# proxmark3.net
KiCad netlist of a schematic drawn in EAGLE
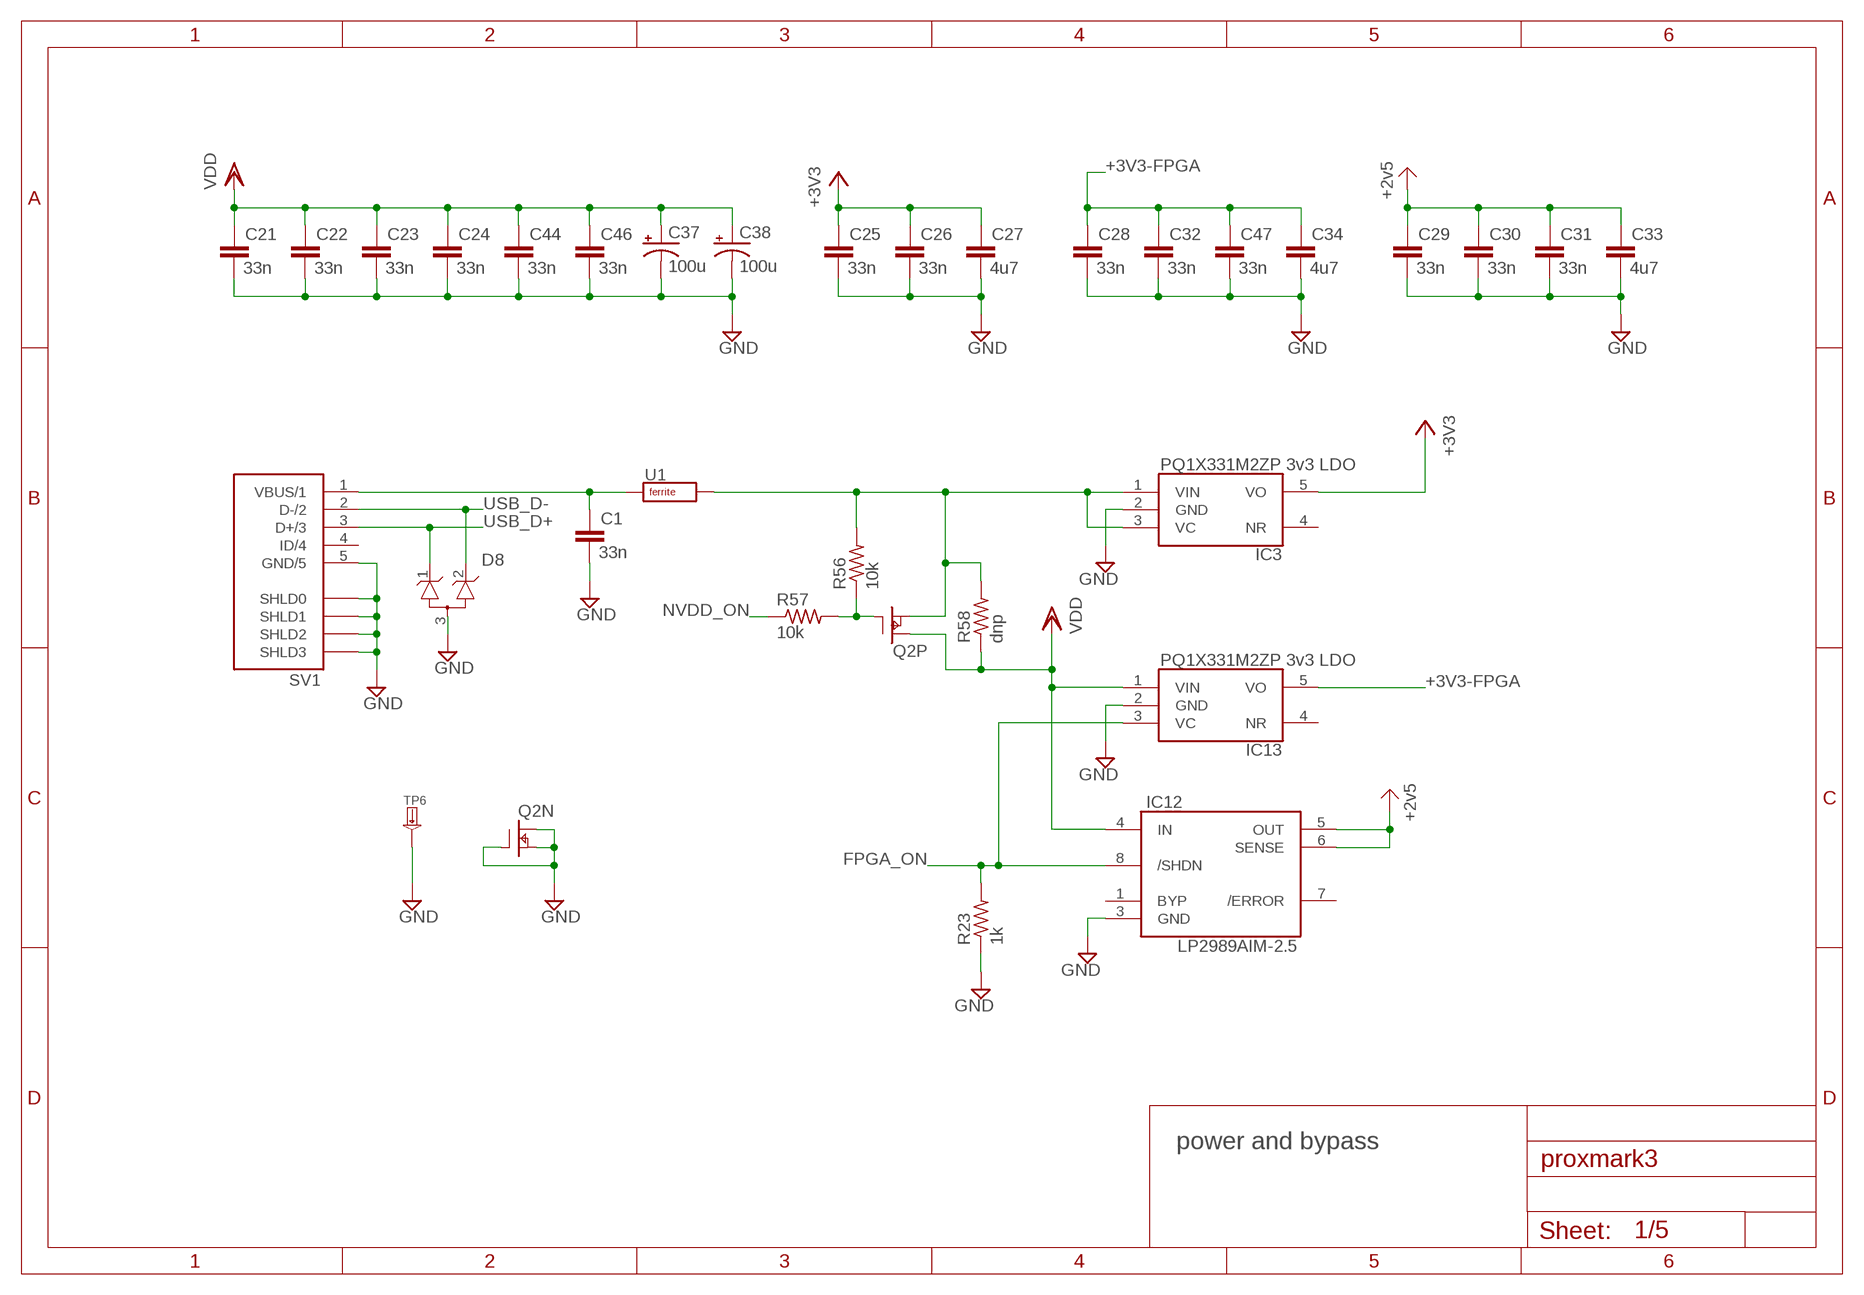
[diagram p0: schematic, sheet 1]
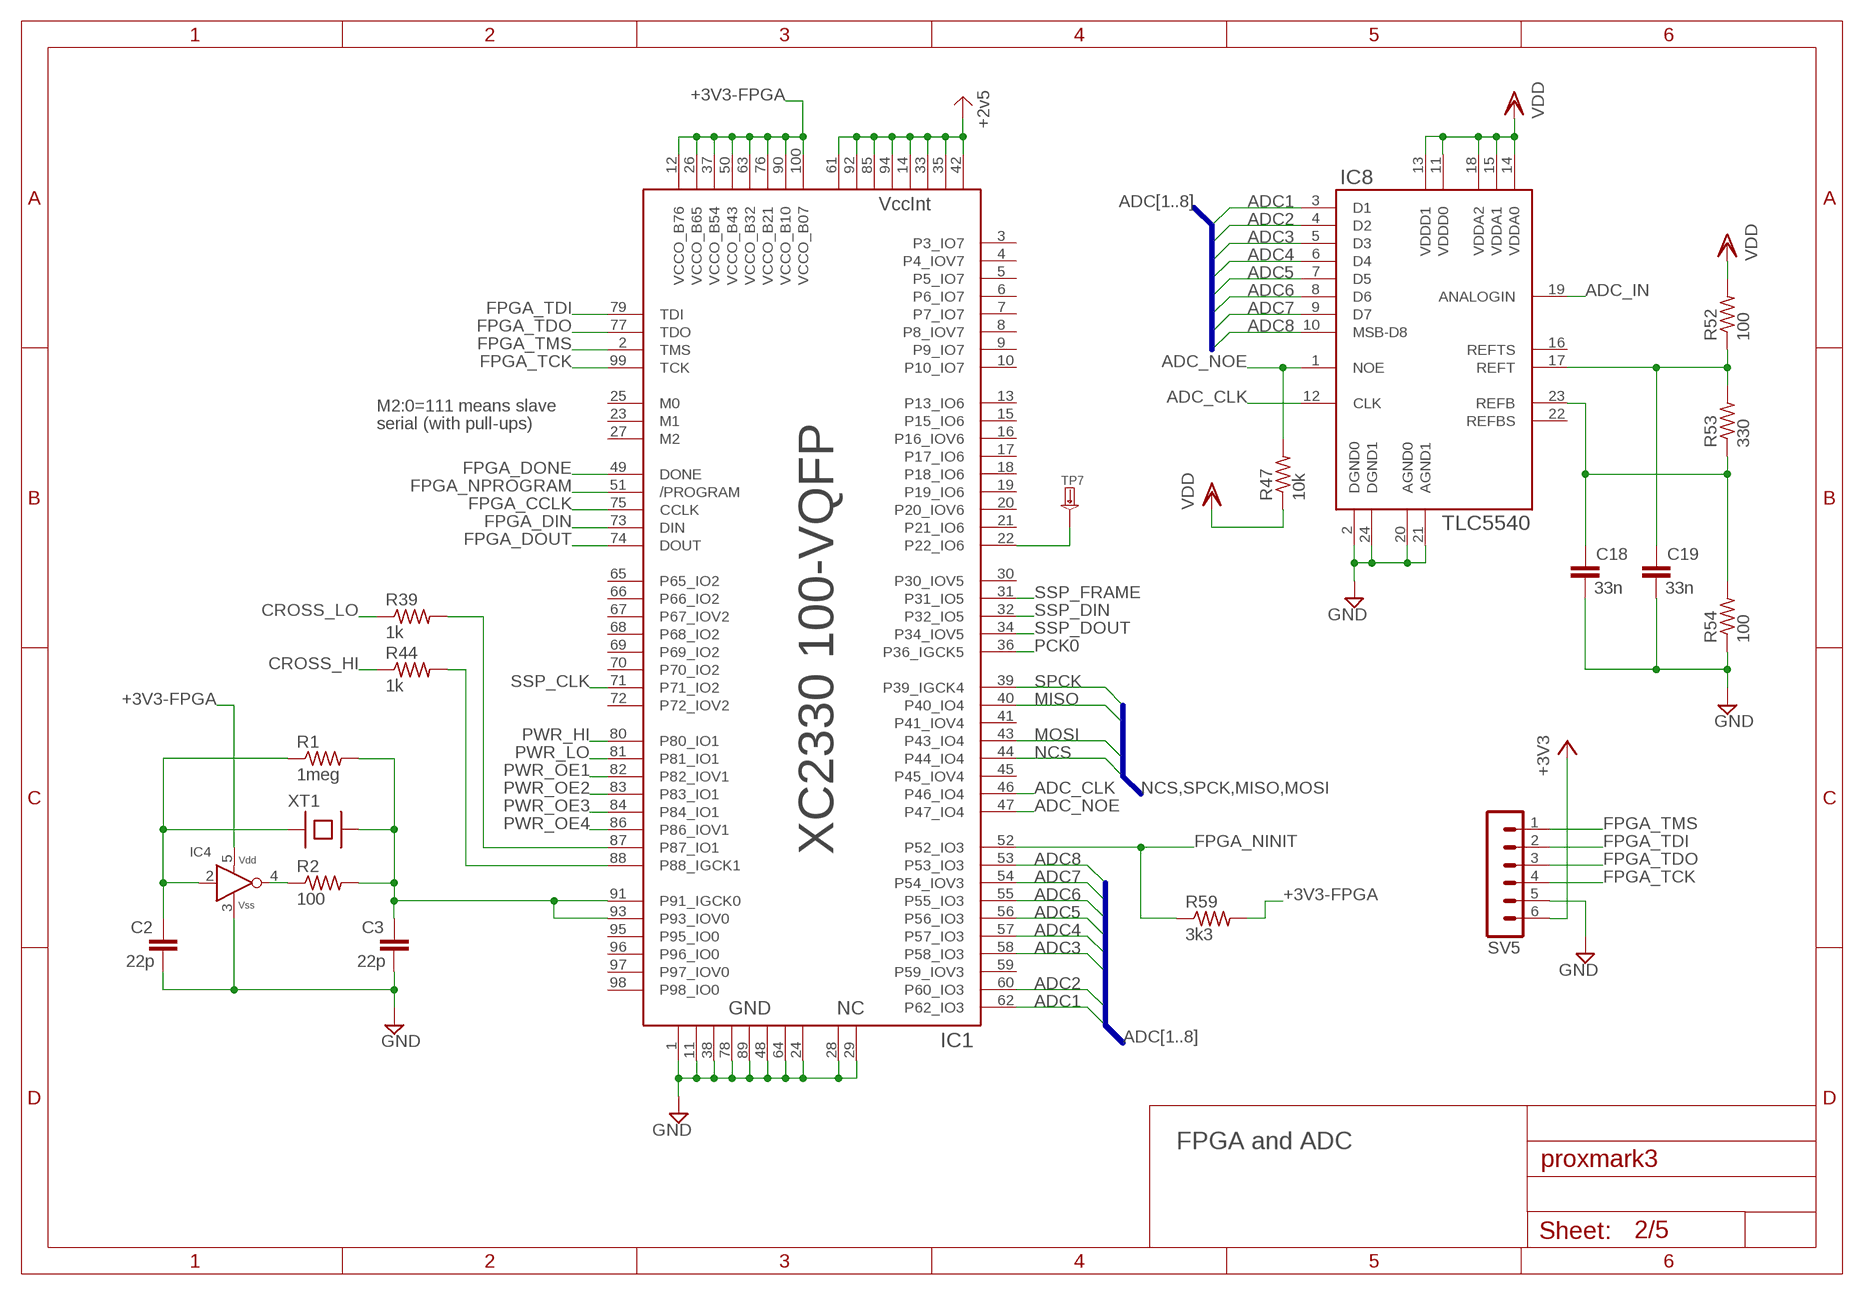
[diagram p1: schematic, sheet 2]
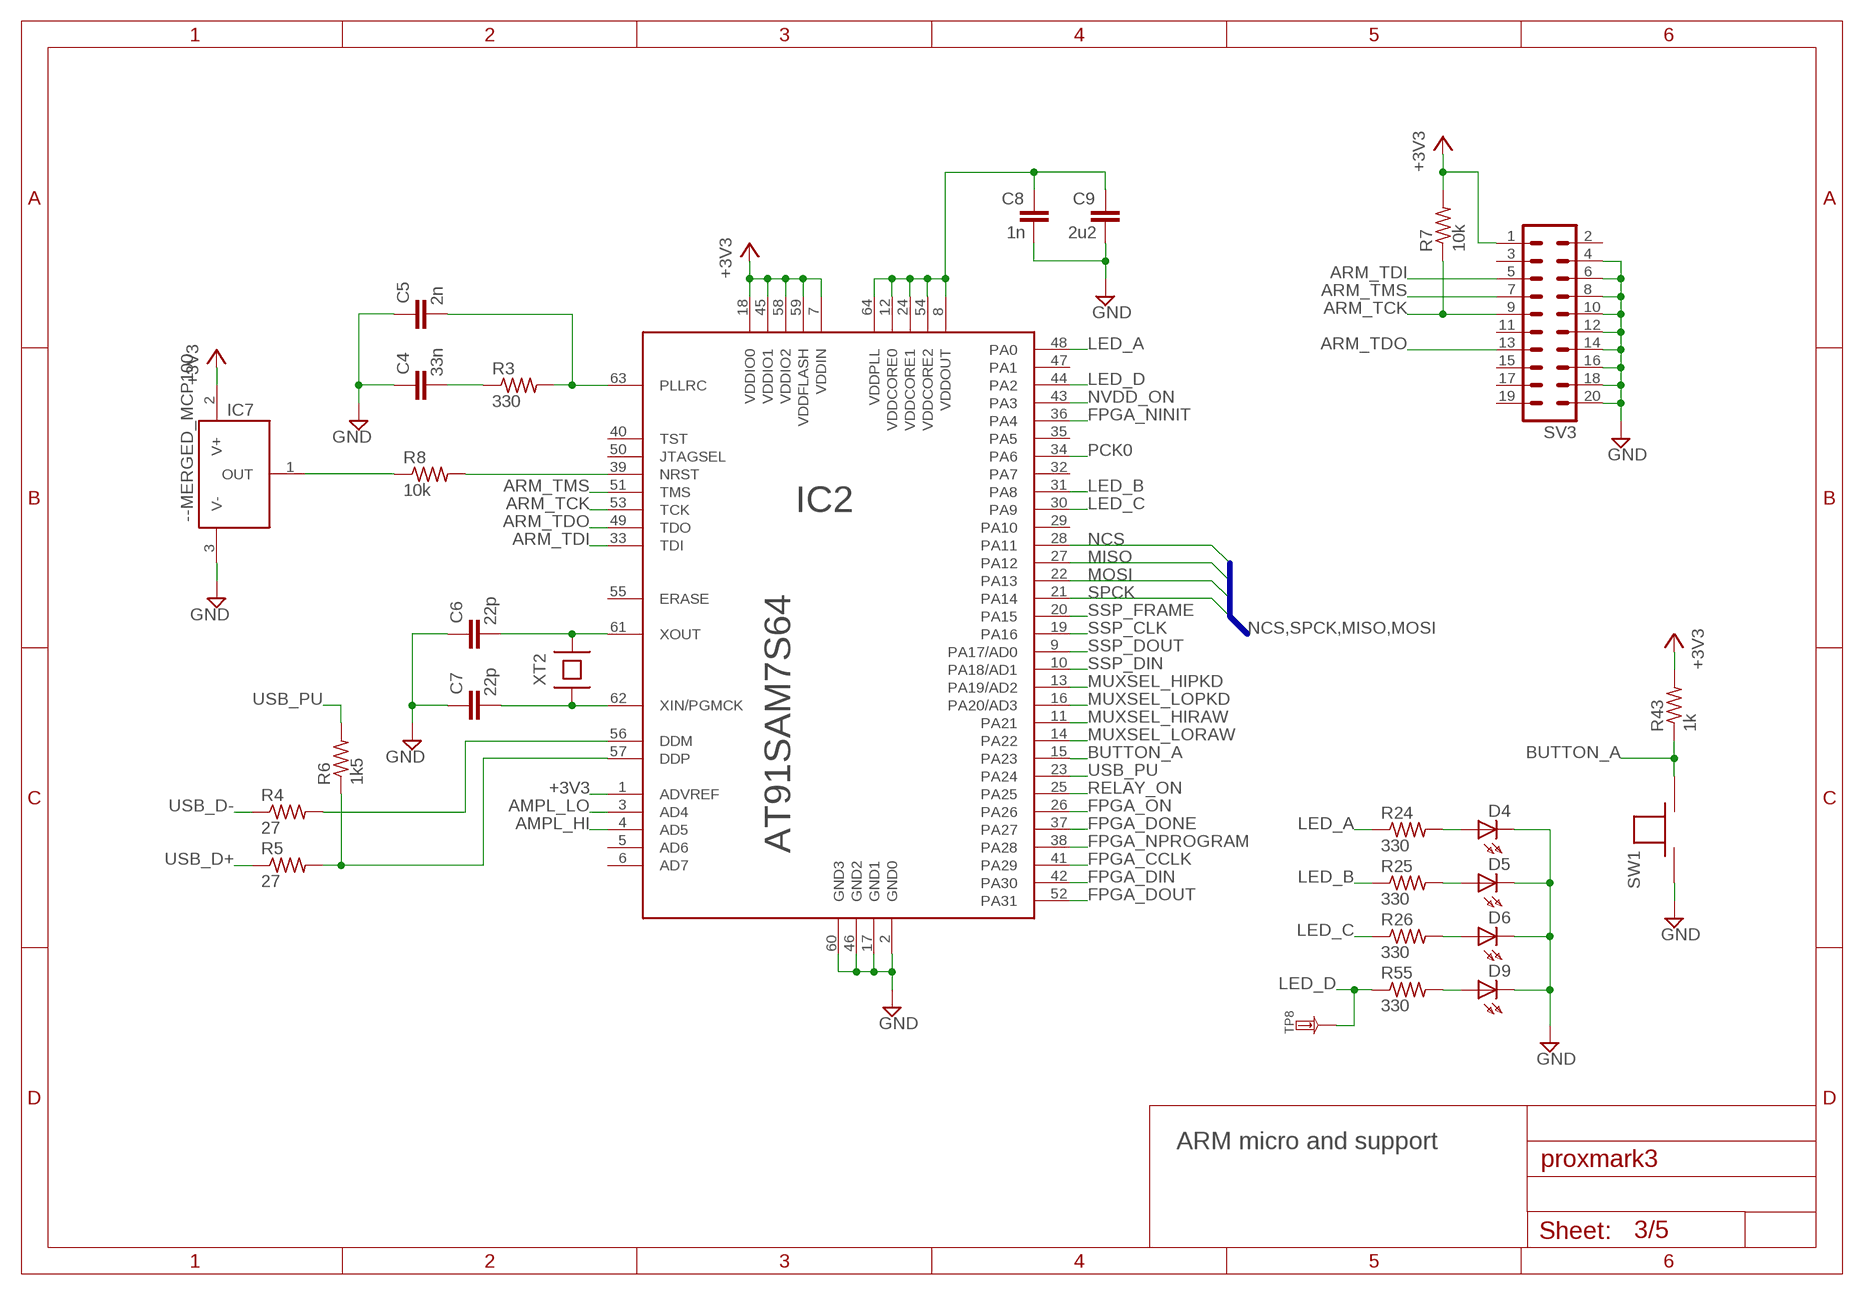
[diagram p2: schematic, sheet 3]
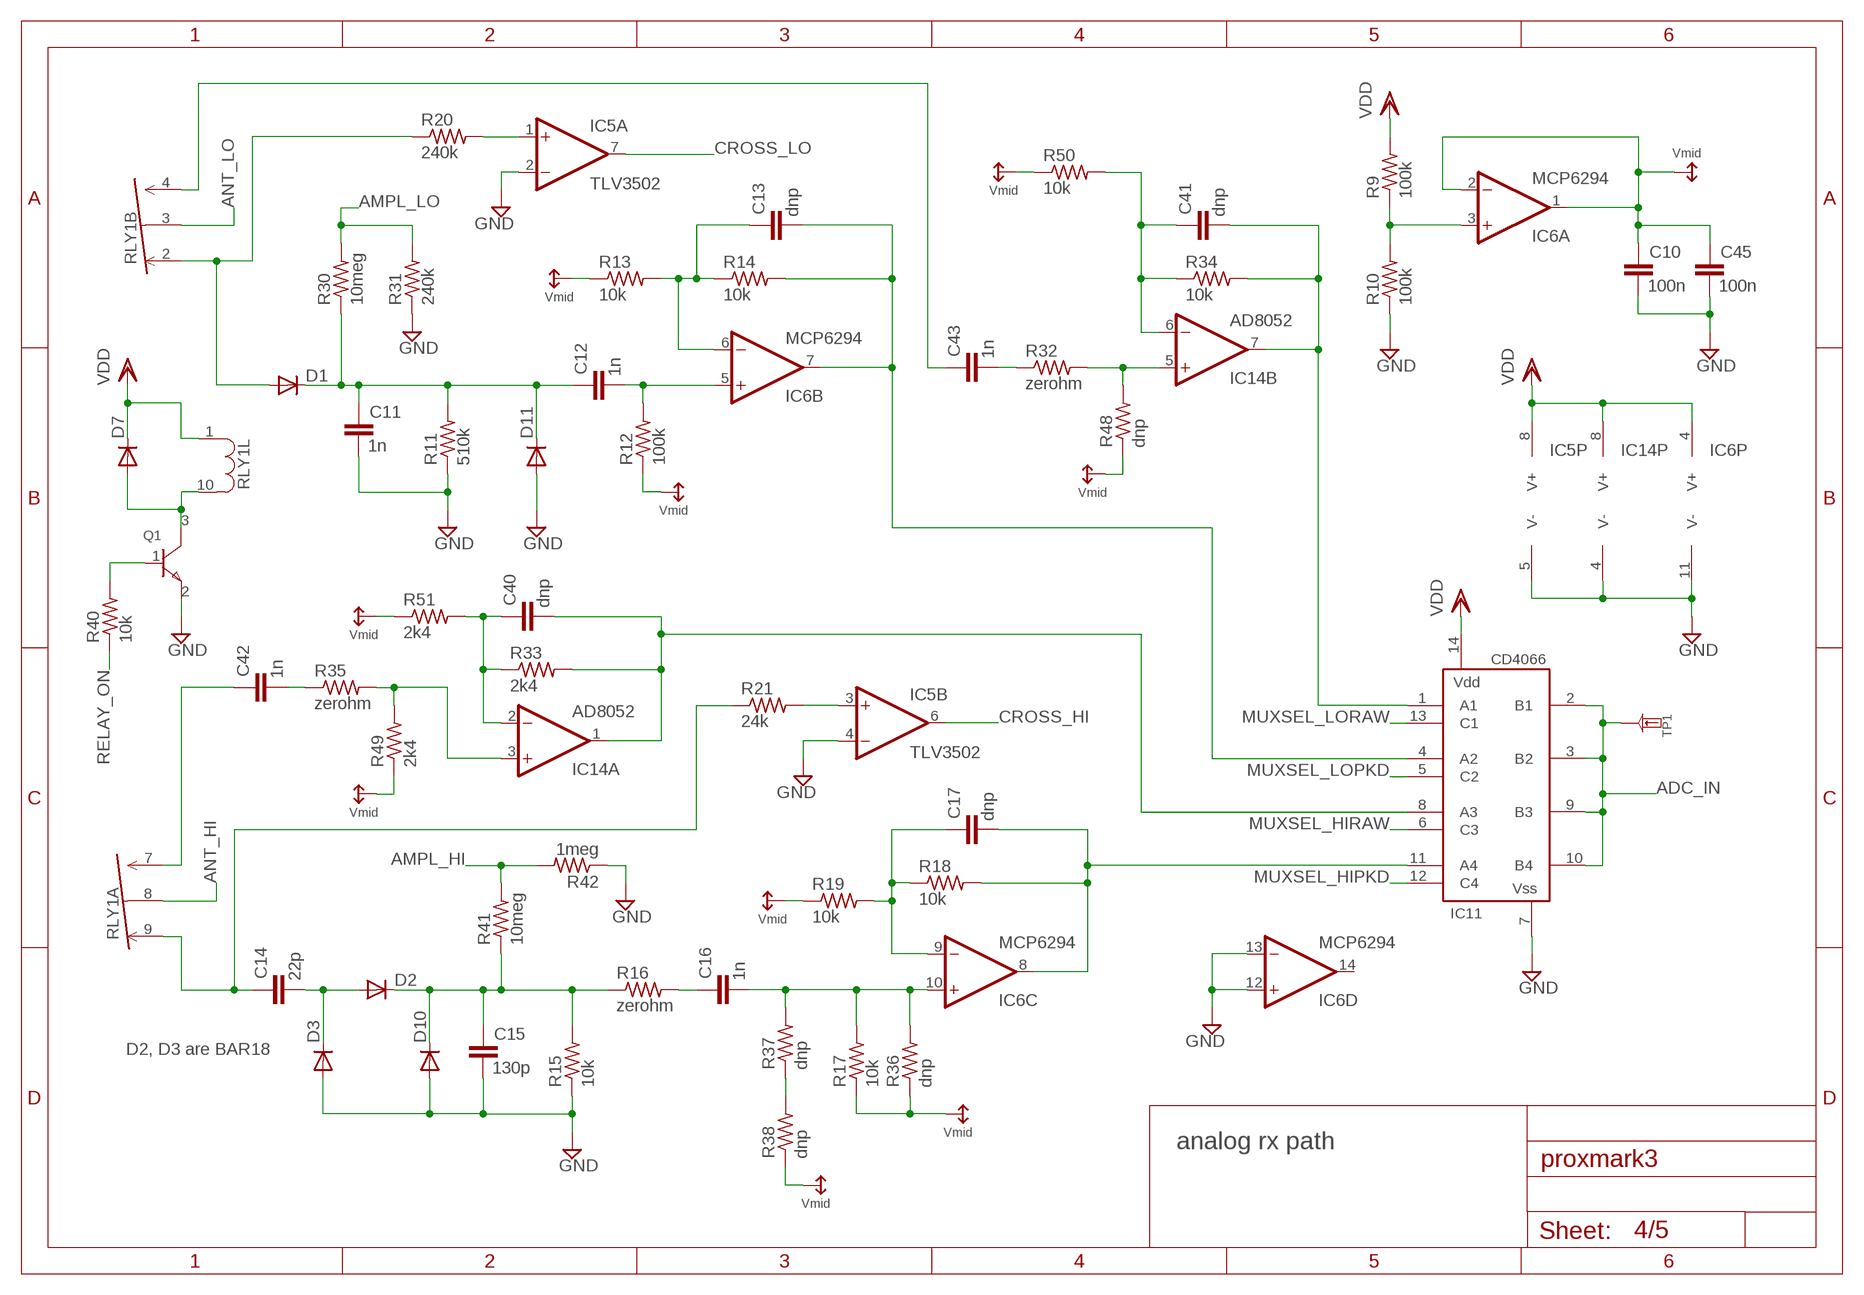
[diagram p3: schematic, sheet 4]
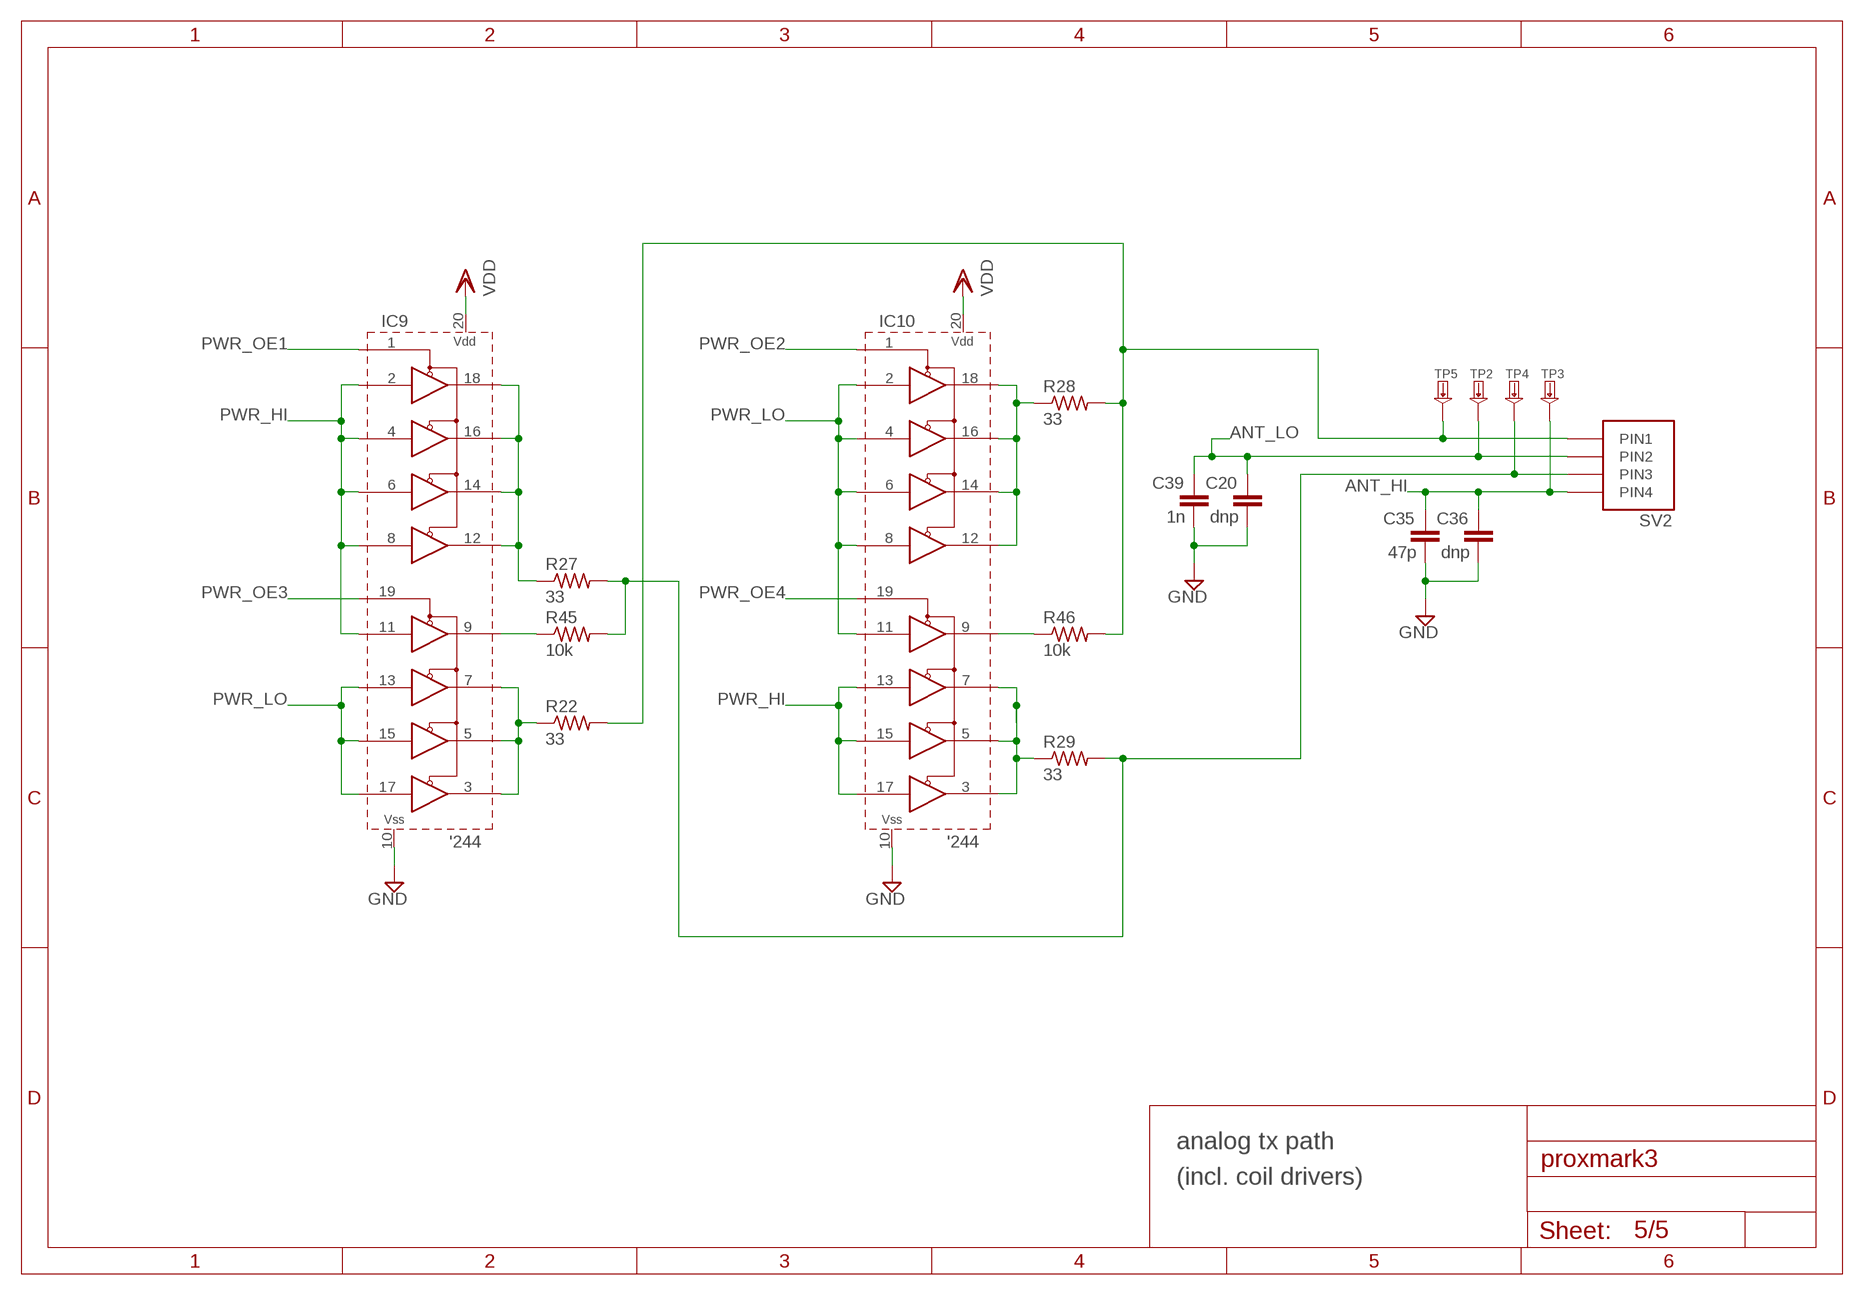
[diagram p4: schematic, sheet 5]

(export (version "E")
  (design (tool "Eeschema 10.0.6"))
  (components
    (comp (ref "C1")
      (value "33n")
      (footprint "eagle-import:RLC_0603")
      (libsource (lib "eagle-import") (part "CAPACITOR0603"))
    )
    (comp (ref "C21")
      (value "33n")
      (footprint "eagle-import:RLC_0603")
      (libsource (lib "eagle-import") (part "CAPACITOR0603"))
    )
    (comp (ref "C22")
      (value "33n")
      (footprint "eagle-import:RLC_0603")
      (libsource (lib "eagle-import") (part "CAPACITOR0603"))
    )
    (comp (ref "C23")
      (value "33n")
      (footprint "eagle-import:RLC_0603")
      (libsource (lib "eagle-import") (part "CAPACITOR0603"))
    )
    (comp (ref "C24")
      (value "33n")
      (footprint "eagle-import:RLC_0603")
      (libsource (lib "eagle-import") (part "CAPACITOR0603"))
    )
    (comp (ref "C25")
      (value "33n")
      (footprint "eagle-import:RLC_0603")
      (libsource (lib "eagle-import") (part "CAPACITOR0603"))
    )
    (comp (ref "C26")
      (value "33n")
      (footprint "eagle-import:RLC_0603")
      (libsource (lib "eagle-import") (part "CAPACITOR0603"))
    )
    (comp (ref "C27")
      (value "4u7")
      (footprint "eagle-import:RLC_1210")
      (libsource (lib "eagle-import") (part "CAPACITOR1210"))
    )
    (comp (ref "C28")
      (value "33n")
      (footprint "eagle-import:RLC_0603")
      (libsource (lib "eagle-import") (part "CAPACITOR0603"))
    )
    (comp (ref "C29")
      (value "33n")
      (footprint "eagle-import:RLC_0603")
      (libsource (lib "eagle-import") (part "CAPACITOR0603"))
    )
    (comp (ref "C30")
      (value "33n")
      (footprint "eagle-import:RLC_0603")
      (libsource (lib "eagle-import") (part "CAPACITOR0603"))
    )
    (comp (ref "C31")
      (value "33n")
      (footprint "eagle-import:RLC_0603")
      (libsource (lib "eagle-import") (part "CAPACITOR0603"))
    )
    (comp (ref "C32")
      (value "33n")
      (footprint "eagle-import:RLC_0603")
      (libsource (lib "eagle-import") (part "CAPACITOR0603"))
    )
    (comp (ref "C33")
      (value "4u7")
      (footprint "eagle-import:RLC_1210")
      (libsource (lib "eagle-import") (part "CAPACITOR1210"))
    )
    (comp (ref "C34")
      (value "4u7")
      (footprint "eagle-import:RLC_1210")
      (libsource (lib "eagle-import") (part "CAPACITOR1210"))
    )
    (comp (ref "C37")
      (value "100u")
      (footprint "eagle-import:CAPCAITOR-ELECTROLYTIC-ALCHIP-MZA-F80")
      (libsource (lib "eagle-import") (part "CAPACITOR-POLARIZEDALCHIP-MZA-F80"))
    )
    (comp (ref "C38")
      (value "100u")
      (footprint "eagle-import:CAPCAITOR-ELECTROLYTIC-ALCHIP-MZA-F80")
      (libsource (lib "eagle-import") (part "CAPACITOR-POLARIZEDALCHIP-MZA-F80"))
    )
    (comp (ref "C44")
      (value "33n")
      (footprint "eagle-import:RLC_0603")
      (libsource (lib "eagle-import") (part "CAPACITOR0603"))
    )
    (comp (ref "C46")
      (value "33n")
      (footprint "eagle-import:RLC_0603")
      (libsource (lib "eagle-import") (part "CAPACITOR0603"))
    )
    (comp (ref "C47")
      (value "33n")
      (footprint "eagle-import:RLC_0603")
      (libsource (lib "eagle-import") (part "CAPACITOR0603"))
    )
    (comp (ref "D8")
      (value "--MERGED_DUAL-TVS-COMMON-ANODE")
      (footprint "eagle-import:--MERGED_SOT23-3LEAD")
      (libsource (lib "eagle-import") (part "--MERGED_DUAL-TVS-COMMON-ANODE"))
    )
    (comp (ref "IC3")
      (value "--MERGED_PQ1X331M2ZP-3V3-LDO-SOT-23-5")
      (footprint "eagle-import:--MERGED_SOT-23-5")
      (libsource (lib "eagle-import") (part "--MERGED_PQ1X331M2ZP-3V3-LDO-SOT-23-5"))
    )
    (comp (ref "IC12")
      (value "LP2989AIM-2.5")
      (footprint "eagle-import:SOIC-8")
      (libsource (lib "eagle-import") (part "LP2989-LDOSOIC"))
    )
    (comp (ref "IC13")
      (value "--MERGED_PQ1X331M2ZP-3V3-LDO-SOT-23-5")
      (footprint "eagle-import:--MERGED_SOT-23-5")
      (libsource (lib "eagle-import") (part "--MERGED_PQ1X331M2ZP-3V3-LDO-SOT-23-5"))
    )
    (comp (ref "Q2")
      (value "IRF7307")
      (footprint "eagle-import:SOIC-8")
      (libsource (lib "eagle-import") (part "IRF7307"))
    )
    (comp (ref "R23")
      (value "1k")
      (footprint "eagle-import:RLC_0603")
      (libsource (lib "eagle-import") (part "RESISTOR0603"))
    )
    (comp (ref "R56")
      (value "10k")
      (footprint "eagle-import:RLC_0603")
      (libsource (lib "eagle-import") (part "RESISTOR0603"))
    )
    (comp (ref "R57")
      (value "10k")
      (footprint "eagle-import:RLC_0603")
      (libsource (lib "eagle-import") (part "RESISTOR0603"))
    )
    (comp (ref "R58")
      (value "dnp")
      (footprint "eagle-import:RLC_0603")
      (libsource (lib "eagle-import") (part "RESISTOR0603"))
    )
    (comp (ref "SV1")
      (value "USB-MINIB")
      (footprint "eagle-import:USB-MINIB-SMD")
      (libsource (lib "eagle-import") (part "USB-MINIB"))
    )
    (comp (ref "TP6")
      (value "TESTPADKEYSTONE-PTH")
      (footprint "eagle-import:KEYSTONE-PTH-TESTPOINT-5011")
      (libsource (lib "eagle-import") (part "TESTPADKEYSTONE-PTH"))
    )
    (comp (ref "U1")
      (value "FERRITE0805")
      (footprint "eagle-import:RLC_0805")
      (libsource (lib "eagle-import") (part "FERRITE0805"))
    )
    (comp (ref "C20")
      (value "dnp")
      (footprint "eagle-import:RLC_0603")
      (libsource (lib "eagle-import") (part "CAPACITOR0603"))
    )
    (comp (ref "C35")
      (value "47p")
      (footprint "eagle-import:RLC_0603")
      (libsource (lib "eagle-import") (part "CAPACITOR0603"))
    )
    (comp (ref "C36")
      (value "dnp")
      (footprint "eagle-import:RLC_0603")
      (libsource (lib "eagle-import") (part "CAPACITOR0603"))
    )
    (comp (ref "C39")
      (value "1n")
      (footprint "eagle-import:RLC_0603")
      (libsource (lib "eagle-import") (part "CAPACITOR0603"))
    )
    (comp (ref "IC9")
      (value "74XX244-OCTAL-TRISTATE-BUFFERS")
      (footprint "eagle-import:TSSOP-20")
      (libsource (lib "eagle-import") (part "74XX244-OCTAL-TRISTATE-BUFFERS"))
    )
    (comp (ref "IC10")
      (value "74XX244-OCTAL-TRISTATE-BUFFERS")
      (footprint "eagle-import:TSSOP-20")
      (libsource (lib "eagle-import") (part "74XX244-OCTAL-TRISTATE-BUFFERS"))
    )
    (comp (ref "R22")
      (value "33")
      (footprint "eagle-import:RLC_0603")
      (libsource (lib "eagle-import") (part "RESISTOR0603"))
    )
    (comp (ref "R27")
      (value "33")
      (footprint "eagle-import:RLC_0603")
      (libsource (lib "eagle-import") (part "RESISTOR0603"))
    )
    (comp (ref "R28")
      (value "33")
      (footprint "eagle-import:RLC_0603")
      (libsource (lib "eagle-import") (part "RESISTOR0603"))
    )
    (comp (ref "R29")
      (value "33")
      (footprint "eagle-import:RLC_0603")
      (libsource (lib "eagle-import") (part "RESISTOR0603"))
    )
    (comp (ref "R45")
      (value "10k")
      (footprint "eagle-import:RLC_0603")
      (libsource (lib "eagle-import") (part "RESISTOR0603"))
    )
    (comp (ref "R46")
      (value "10k")
      (footprint "eagle-import:RLC_0603")
      (libsource (lib "eagle-import") (part "RESISTOR0603"))
    )
    (comp (ref "SV2")
      (value "HIROSE-MQ172-4POS")
      (footprint "eagle-import:HIROSE-MQ172-4POS")
      (libsource (lib "eagle-import") (part "HIROSE-MQ172-4POS"))
    )
    (comp (ref "TP2")
      (value "TESTPADKEYSTONE-SMD")
      (footprint "eagle-import:KEYSTONE-SMD-TESTPOINT-5015")
      (libsource (lib "eagle-import") (part "TESTPADKEYSTONE-SMD"))
    )
    (comp (ref "TP3")
      (value "TESTPADKEYSTONE-SMD")
      (footprint "eagle-import:KEYSTONE-SMD-TESTPOINT-5015")
      (libsource (lib "eagle-import") (part "TESTPADKEYSTONE-SMD"))
    )
    (comp (ref "TP4")
      (value "TESTPADKEYSTONE-SMD")
      (footprint "eagle-import:KEYSTONE-SMD-TESTPOINT-5015")
      (libsource (lib "eagle-import") (part "TESTPADKEYSTONE-SMD"))
    )
    (comp (ref "TP5")
      (value "TESTPADKEYSTONE-SMD")
      (footprint "eagle-import:KEYSTONE-SMD-TESTPOINT-5015")
      (libsource (lib "eagle-import") (part "TESTPADKEYSTONE-SMD"))
    )
    (comp (ref "C2")
      (value "22p")
      (footprint "eagle-import:RLC_0603")
      (libsource (lib "eagle-import") (part "CAPACITOR0603"))
    )
    (comp (ref "C3")
      (value "22p")
      (footprint "eagle-import:RLC_0603")
      (libsource (lib "eagle-import") (part "CAPACITOR0603"))
    )
    (comp (ref "C18")
      (value "33n")
      (footprint "eagle-import:RLC_0603")
      (libsource (lib "eagle-import") (part "CAPACITOR0603"))
    )
    (comp (ref "C19")
      (value "33n")
      (footprint "eagle-import:RLC_0603")
      (libsource (lib "eagle-import") (part "CAPACITOR0603"))
    )
    (comp (ref "IC1")
      (value "SPARTAN-II-XC2S30-100-VQFP")
      (footprint "eagle-import:VQFP-100")
      (libsource (lib "eagle-import") (part "SPARTAN-II-XC2S30-100-VQFP"))
    )
    (comp (ref "IC4")
      (value "HCU-INVERTER")
      (footprint "eagle-import:SMV-5")
      (libsource (lib "eagle-import") (part "HCU-INVERTER"))
    )
    (comp (ref "IC8")
      (value "TLC5540")
      (footprint "eagle-import:TSSOP-24")
      (libsource (lib "eagle-import") (part "TLC5540"))
    )
    (comp (ref "R1")
      (value "1meg")
      (footprint "eagle-import:RLC_0603")
      (libsource (lib "eagle-import") (part "RESISTOR0603"))
    )
    (comp (ref "R2")
      (value "100")
      (footprint "eagle-import:RLC_0603")
      (libsource (lib "eagle-import") (part "RESISTOR0603"))
    )
    (comp (ref "R39")
      (value "1k")
      (footprint "eagle-import:RLC_0603")
      (libsource (lib "eagle-import") (part "RESISTOR0603"))
    )
    (comp (ref "R44")
      (value "1k")
      (footprint "eagle-import:RLC_0603")
      (libsource (lib "eagle-import") (part "RESISTOR0603"))
    )
    (comp (ref "R47")
      (value "10k")
      (footprint "eagle-import:RLC_0603")
      (libsource (lib "eagle-import") (part "RESISTOR0603"))
    )
    (comp (ref "R52")
      (value "100")
      (footprint "eagle-import:RLC_0603")
      (libsource (lib "eagle-import") (part "RESISTOR0603"))
    )
    (comp (ref "R53")
      (value "330")
      (footprint "eagle-import:RLC_0603")
      (libsource (lib "eagle-import") (part "RESISTOR0603"))
    )
    (comp (ref "R54")
      (value "100")
      (footprint "eagle-import:RLC_0603")
      (libsource (lib "eagle-import") (part "RESISTOR0603"))
    )
    (comp (ref "R59")
      (value "3k3")
      (footprint "eagle-import:RLC_0603")
      (libsource (lib "eagle-import") (part "RESISTOR0603"))
    )
    (comp (ref "SV5")
      (value "--MERGED_HEADER-MALE-6X1")
      (footprint "eagle-import:--MERGED_HEADER-MALE-6X1-0.100-UNKEYED")
      (libsource (lib "eagle-import") (part "--MERGED_HEADER-MALE-6X1"))
    )
    (comp (ref "TP7")
      (value "TESTPADKEYSTONE-SMD")
      (footprint "eagle-import:KEYSTONE-SMD-TESTPOINT-5015")
      (libsource (lib "eagle-import") (part "TESTPADKEYSTONE-SMD"))
    )
    (comp (ref "XT1")
      (value "XTAL-SMD-CITIZEN-CS10")
      (footprint "eagle-import:XTAL-SMD-CITIZEN-CS10")
      (libsource (lib "eagle-import") (part "XTAL-SMD-CITIZEN-CS10"))
    )
    (comp (ref "C4")
      (value "33n")
      (footprint "eagle-import:RLC_0603")
      (libsource (lib "eagle-import") (part "CAPACITOR0603"))
    )
    (comp (ref "C5")
      (value "2n")
      (footprint "eagle-import:RLC_0603")
      (libsource (lib "eagle-import") (part "CAPACITOR0603"))
    )
    (comp (ref "C6")
      (value "22p")
      (footprint "eagle-import:--MERGED_RLC_0603")
      (libsource (lib "eagle-import") (part "--MERGED_CAPACITOR0603"))
    )
    (comp (ref "C7")
      (value "22p")
      (footprint "eagle-import:--MERGED_RLC_0603")
      (libsource (lib "eagle-import") (part "--MERGED_CAPACITOR0603"))
    )
    (comp (ref "C8")
      (value "1n")
      (footprint "eagle-import:RLC_0603")
      (libsource (lib "eagle-import") (part "CAPACITOR0603"))
    )
    (comp (ref "C9")
      (value "2u2")
      (footprint "eagle-import:RLC_1210")
      (libsource (lib "eagle-import") (part "CAPACITOR1210"))
    )
    (comp (ref "D4")
      (value "LED")
      (footprint "eagle-import:LED_0603")
      (libsource (lib "eagle-import") (part "LED"))
    )
    (comp (ref "D5")
      (value "LED")
      (footprint "eagle-import:LED_0603")
      (libsource (lib "eagle-import") (part "LED"))
    )
    (comp (ref "D6")
      (value "LED")
      (footprint "eagle-import:LED_0603")
      (libsource (lib "eagle-import") (part "LED"))
    )
    (comp (ref "D9")
      (value "LED")
      (footprint "eagle-import:LED_0603")
      (libsource (lib "eagle-import") (part "LED"))
    )
    (comp (ref "IC2")
      (value "AT91SAM7S64")
      (footprint "eagle-import:LQFP-64")
      (libsource (lib "eagle-import") (part "AT91SAM7S64"))
    )
    (comp (ref "IC7")
      (value "--MERGED_MCP100")
      (footprint "eagle-import:--MERGED_SOT23-3LEAD")
      (libsource (lib "eagle-import") (part "--MERGED_MCP100"))
    )
    (comp (ref "R3")
      (value "330")
      (footprint "eagle-import:RLC_0603")
      (libsource (lib "eagle-import") (part "RESISTOR0603"))
    )
    (comp (ref "R4")
      (value "27")
      (footprint "eagle-import:RLC_0603")
      (libsource (lib "eagle-import") (part "RESISTOR0603"))
    )
    (comp (ref "R5")
      (value "27")
      (footprint "eagle-import:RLC_0603")
      (libsource (lib "eagle-import") (part "RESISTOR0603"))
    )
    (comp (ref "R6")
      (value "1k5")
      (footprint "eagle-import:RLC_0603")
      (libsource (lib "eagle-import") (part "RESISTOR0603"))
    )
    (comp (ref "R7")
      (value "10k")
      (footprint "eagle-import:RLC_0603")
      (libsource (lib "eagle-import") (part "RESISTOR0603"))
    )
    (comp (ref "R8")
      (value "10k")
      (footprint "eagle-import:RLC_0603")
      (libsource (lib "eagle-import") (part "RESISTOR0603"))
    )
    (comp (ref "R24")
      (value "330")
      (footprint "eagle-import:RLC_0603")
      (libsource (lib "eagle-import") (part "RESISTOR0603"))
    )
    (comp (ref "R25")
      (value "330")
      (footprint "eagle-import:RLC_0603")
      (libsource (lib "eagle-import") (part "RESISTOR0603"))
    )
    (comp (ref "R26")
      (value "330")
      (footprint "eagle-import:RLC_0603")
      (libsource (lib "eagle-import") (part "RESISTOR0603"))
    )
    (comp (ref "R43")
      (value "1k")
      (footprint "eagle-import:RLC_0603")
      (libsource (lib "eagle-import") (part "RESISTOR0603"))
    )
    (comp (ref "R55")
      (value "330")
      (footprint "eagle-import:RLC_0603")
      (libsource (lib "eagle-import") (part "RESISTOR0603"))
    )
    (comp (ref "SV3")
      (value "HEADER-MALE-10X2")
      (footprint "eagle-import:HEADER-MALE-10X2-0.100-SHROUDED")
      (libsource (lib "eagle-import") (part "HEADER-MALE-10X2"))
    )
    (comp (ref "SW1")
      (value "TACTSWITCH")
      (footprint "eagle-import:TACTSWITCH-SMD-EVQQ1")
      (libsource (lib "eagle-import") (part "TACTSWITCH"))
    )
    (comp (ref "TP8")
      (value "TESTPADKEYSTONE-SMD")
      (footprint "eagle-import:KEYSTONE-SMD-TESTPOINT-5015")
      (libsource (lib "eagle-import") (part "TESTPADKEYSTONE-SMD"))
    )
    (comp (ref "XT2")
      (value "XTAL-SMD-CITIZEN-CS10")
      (footprint "eagle-import:XTAL-SMD-CITIZEN-CS10")
      (libsource (lib "eagle-import") (part "XTAL-SMD-CITIZEN-CS10"))
    )
    (comp (ref "C10")
      (value "100n")
      (footprint "eagle-import:RLC_0603")
      (libsource (lib "eagle-import") (part "CAPACITOR0603"))
    )
    (comp (ref "C11")
      (value "1n")
      (footprint "eagle-import:RLC_0603")
      (libsource (lib "eagle-import") (part "CAPACITOR0603"))
    )
    (comp (ref "C12")
      (value "1n")
      (footprint "eagle-import:RLC_0603")
      (libsource (lib "eagle-import") (part "CAPACITOR0603"))
    )
    (comp (ref "C13")
      (value "dnp")
      (footprint "eagle-import:RLC_0603")
      (libsource (lib "eagle-import") (part "CAPACITOR0603"))
    )
    (comp (ref "C14")
      (value "22p")
      (footprint "eagle-import:RLC_0603")
      (libsource (lib "eagle-import") (part "CAPACITOR0603"))
    )
    (comp (ref "C15")
      (value "130p")
      (footprint "eagle-import:RLC_0603")
      (libsource (lib "eagle-import") (part "CAPACITOR0603"))
    )
    (comp (ref "C16")
      (value "1n")
      (footprint "eagle-import:RLC_0603")
      (libsource (lib "eagle-import") (part "CAPACITOR0603"))
    )
    (comp (ref "C17")
      (value "dnp")
      (footprint "eagle-import:RLC_0603")
      (libsource (lib "eagle-import") (part "CAPACITOR0603"))
    )
    (comp (ref "C40")
      (value "dnp")
      (footprint "eagle-import:RLC_0603")
      (libsource (lib "eagle-import") (part "CAPACITOR0603"))
    )
    (comp (ref "C41")
      (value "dnp")
      (footprint "eagle-import:RLC_0603")
      (libsource (lib "eagle-import") (part "CAPACITOR0603"))
    )
    (comp (ref "C42")
      (value "1n")
      (footprint "eagle-import:RLC_0603")
      (libsource (lib "eagle-import") (part "CAPACITOR0603"))
    )
    (comp (ref "C43")
      (value "1n")
      (footprint "eagle-import:RLC_0603")
      (libsource (lib "eagle-import") (part "CAPACITOR0603"))
    )
    (comp (ref "C45")
      (value "100n")
      (footprint "eagle-import:RLC_0603")
      (libsource (lib "eagle-import") (part "CAPACITOR0603"))
    )
    (comp (ref "D1")
      (value "--MERGED_DIODE-SMD-SOT23")
      (footprint "eagle-import:--MERGED_SOT23-3LEAD")
      (libsource (lib "eagle-import") (part "--MERGED_DIODE-SMD-SOT23"))
    )
    (comp (ref "D2")
      (value "--MERGED_DIODE-SMD-SOT23")
      (footprint "eagle-import:--MERGED_SOT23-3LEAD")
      (libsource (lib "eagle-import") (part "--MERGED_DIODE-SMD-SOT23"))
    )
    (comp (ref "D3")
      (value "--MERGED_DIODE-SMD-SOT23")
      (footprint "eagle-import:--MERGED_SOT23-3LEAD")
      (libsource (lib "eagle-import") (part "--MERGED_DIODE-SMD-SOT23"))
    )
    (comp (ref "D7")
      (value "--MERGED_DIODE-SMD-SOT23")
      (footprint "eagle-import:--MERGED_SOT23-3LEAD")
      (libsource (lib "eagle-import") (part "--MERGED_DIODE-SMD-SOT23"))
    )
    (comp (ref "D10")
      (value "--MERGED_DIODE-SMD-SOT23")
      (footprint "eagle-import:--MERGED_SOT23-3LEAD")
      (libsource (lib "eagle-import") (part "--MERGED_DIODE-SMD-SOT23"))
    )
    (comp (ref "D11")
      (value "--MERGED_DIODE-SMD-SOT23")
      (footprint "eagle-import:--MERGED_SOT23-3LEAD")
      (libsource (lib "eagle-import") (part "--MERGED_DIODE-SMD-SOT23"))
    )
    (comp (ref "IC5")
      (value "TLV3502")
      (footprint "eagle-import:SOT-23-8-OR-MSOP-8")
      (libsource (lib "eagle-import") (part "COMP-TLV3502SOT-23-8-OR-MSOP-8"))
    )
    (comp (ref "IC6")
      (value "MCP6294")
      (footprint "eagle-import:TSSOP-14")
      (libsource (lib "eagle-import") (part "OPAMP-TLC2274"))
    )
    (comp (ref "IC11")
      (value "CD4066")
      (footprint "eagle-import:TSSOP-14")
      (libsource (lib "eagle-import") (part "CD4066"))
    )
    (comp (ref "IC14")
      (value "AD8052")
      (footprint "eagle-import:MSOP8")
      (libsource (lib "eagle-import") (part "OPAMP-AD8052"))
    )
    (comp (ref "Q1")
      (value "--MERGED_NPN-SOT23-2N3904")
      (footprint "eagle-import:--MERGED_SOT23-3LEAD")
      (libsource (lib "eagle-import") (part "--MERGED_NPN-SOT23-2N3904"))
    )
    (comp (ref "R9")
      (value "100k")
      (footprint "eagle-import:RLC_0603")
      (libsource (lib "eagle-import") (part "RESISTOR0603"))
    )
    (comp (ref "R10")
      (value "100k")
      (footprint "eagle-import:RLC_0603")
      (libsource (lib "eagle-import") (part "RESISTOR0603"))
    )
    (comp (ref "R11")
      (value "510k")
      (footprint "eagle-import:RLC_0603")
      (libsource (lib "eagle-import") (part "RESISTOR0603"))
    )
    (comp (ref "R12")
      (value "100k")
      (footprint "eagle-import:RLC_0603")
      (libsource (lib "eagle-import") (part "RESISTOR0603"))
    )
    (comp (ref "R13")
      (value "10k")
      (footprint "eagle-import:RLC_0603")
      (libsource (lib "eagle-import") (part "RESISTOR0603"))
    )
    (comp (ref "R14")
      (value "10k")
      (footprint "eagle-import:RLC_0603")
      (libsource (lib "eagle-import") (part "RESISTOR0603"))
    )
    (comp (ref "R15")
      (value "10k")
      (footprint "eagle-import:RLC_0603")
      (libsource (lib "eagle-import") (part "RESISTOR0603"))
    )
    (comp (ref "R16")
      (value "zerohm")
      (footprint "eagle-import:RLC_0603")
      (libsource (lib "eagle-import") (part "RESISTOR0603"))
    )
    (comp (ref "R17")
      (value "10k")
      (footprint "eagle-import:RLC_0603")
      (libsource (lib "eagle-import") (part "RESISTOR0603"))
    )
    (comp (ref "R18")
      (value "10k")
      (footprint "eagle-import:RLC_0603")
      (libsource (lib "eagle-import") (part "RESISTOR0603"))
    )
    (comp (ref "R19")
      (value "10k")
      (footprint "eagle-import:RLC_0603")
      (libsource (lib "eagle-import") (part "RESISTOR0603"))
    )
    (comp (ref "R20")
      (value "240k")
      (footprint "eagle-import:RLC_0603")
      (libsource (lib "eagle-import") (part "RESISTOR0603"))
    )
    (comp (ref "R21")
      (value "24k")
      (footprint "eagle-import:RLC_0603")
      (libsource (lib "eagle-import") (part "RESISTOR0603"))
    )
    (comp (ref "R30")
      (value "10meg")
      (footprint "eagle-import:RLC_0603")
      (libsource (lib "eagle-import") (part "RESISTOR0603"))
    )
    (comp (ref "R31")
      (value "240k")
      (footprint "eagle-import:RLC_0603")
      (libsource (lib "eagle-import") (part "RESISTOR0603"))
    )
    (comp (ref "R32")
      (value "zerohm")
      (footprint "eagle-import:RLC_0603")
      (libsource (lib "eagle-import") (part "RESISTOR0603"))
    )
    (comp (ref "R33")
      (value "2k4")
      (footprint "eagle-import:RLC_0603")
      (libsource (lib "eagle-import") (part "RESISTOR0603"))
    )
    (comp (ref "R34")
      (value "10k")
      (footprint "eagle-import:RLC_0603")
      (libsource (lib "eagle-import") (part "RESISTOR0603"))
    )
    (comp (ref "R35")
      (value "zerohm")
      (footprint "eagle-import:RLC_0603")
      (libsource (lib "eagle-import") (part "RESISTOR0603"))
    )
    (comp (ref "R36")
      (value "dnp")
      (footprint "eagle-import:RLC_0603")
      (libsource (lib "eagle-import") (part "RESISTOR0603"))
    )
    (comp (ref "R37")
      (value "dnp")
      (footprint "eagle-import:RLC_0603")
      (libsource (lib "eagle-import") (part "RESISTOR0603"))
    )
    (comp (ref "R38")
      (value "dnp")
      (footprint "eagle-import:RLC_0603")
      (libsource (lib "eagle-import") (part "RESISTOR0603"))
    )
    (comp (ref "R40")
      (value "10k")
      (footprint "eagle-import:RLC_0603")
      (libsource (lib "eagle-import") (part "RESISTOR0603"))
    )
    (comp (ref "R41")
      (value "10meg")
      (footprint "eagle-import:RLC_0603")
      (libsource (lib "eagle-import") (part "RESISTOR0603"))
    )
    (comp (ref "R42")
      (value "1meg")
      (footprint "eagle-import:RLC_0603")
      (libsource (lib "eagle-import") (part "RESISTOR0603"))
    )
    (comp (ref "R48")
      (value "dnp")
      (footprint "eagle-import:RLC_0603")
      (libsource (lib "eagle-import") (part "RESISTOR0603"))
    )
    (comp (ref "R49")
      (value "2k4")
      (footprint "eagle-import:RLC_0603")
      (libsource (lib "eagle-import") (part "RESISTOR0603"))
    )
    (comp (ref "R50")
      (value "10k")
      (footprint "eagle-import:RLC_0603")
      (libsource (lib "eagle-import") (part "RESISTOR0603"))
    )
    (comp (ref "R51")
      (value "2k4")
      (footprint "eagle-import:RLC_0603")
      (libsource (lib "eagle-import") (part "RESISTOR0603"))
    )
    (comp (ref "RLY1")
      (value "--MERGED_RELAY-DPDT")
      (footprint "eagle-import:--MERGED_TQ-SMD-RELAY")
      (libsource (lib "eagle-import") (part "--MERGED_RELAY-DPDT"))
    )
    (comp (ref "TP1")
      (value "TESTPADKEYSTONE-SMD")
      (footprint "eagle-import:KEYSTONE-SMD-TESTPOINT-5015")
      (libsource (lib "eagle-import") (part "TESTPADKEYSTONE-SMD"))
    )
  )
  (nets
    (net (code "1") (name "+2V5") (class "Default")
      (node (ref "C29") (pin "1") (pinfunction "1_1") (pintype "passive"))
      (node (ref "C30") (pin "1") (pinfunction "1_1") (pintype "passive"))
      (node (ref "C31") (pin "1") (pinfunction "1_1") (pintype "passive"))
      (node (ref "C33") (pin "1") (pinfunction "1_1") (pintype "passive"))
      (node (ref "IC1") (pin "14") (pinfunction "VCCINT5_14") (pintype "bidirectional"))
      (node (ref "IC1") (pin "33") (pinfunction "VCCINT6_33") (pintype "bidirectional"))
      (node (ref "IC1") (pin "35") (pinfunction "VCCINT7_35") (pintype "bidirectional"))
      (node (ref "IC1") (pin "42") (pinfunction "VCCINT8_42") (pintype "bidirectional"))
      (node (ref "IC1") (pin "61") (pinfunction "VCCINT1_61") (pintype "bidirectional"))
      (node (ref "IC1") (pin "85") (pinfunction "VCCINT3_85") (pintype "bidirectional"))
      (node (ref "IC1") (pin "92") (pinfunction "VCCINT2_92") (pintype "bidirectional"))
      (node (ref "IC1") (pin "94") (pinfunction "VCCINT4_94") (pintype "bidirectional"))
      (node (ref "IC12") (pin "5") (pinfunction "OUT_5") (pintype "passive"))
      (node (ref "IC12") (pin "6") (pinfunction "SENSE_6") (pintype "passive"))
    )
    (net (code "2") (name "+3V3") (class "Default")
      (node (ref "C25") (pin "1") (pinfunction "1_1") (pintype "passive"))
      (node (ref "C26") (pin "1") (pinfunction "1_1") (pintype "passive"))
      (node (ref "C27") (pin "1") (pinfunction "1_1") (pintype "passive"))
      (node (ref "IC2") (pin "1") (pinfunction "ADVREF_1") (pintype "bidirectional"))
      (node (ref "IC2") (pin "18") (pinfunction "VDDIO0_18") (pintype "bidirectional"))
      (node (ref "IC2") (pin "45") (pinfunction "VDDIO1_45") (pintype "bidirectional"))
      (node (ref "IC2") (pin "58") (pinfunction "VDDIO2_58") (pintype "bidirectional"))
      (node (ref "IC2") (pin "59") (pinfunction "VDDFLASH_59") (pintype "bidirectional"))
      (node (ref "IC2") (pin "7") (pinfunction "VDDIN_7") (pintype "bidirectional"))
      (node (ref "IC3") (pin "5") (pinfunction "VO_5") (pintype "bidirectional"))
      (node (ref "IC7") (pin "2") (pinfunction "V+_2") (pintype "bidirectional"))
      (node (ref "R43") (pin "2") (pinfunction "2_2") (pintype "passive"))
      (node (ref "R7") (pin "2") (pinfunction "2_2") (pintype "passive"))
      (node (ref "SV3") (pin "1") (pinfunction "1_1") (pintype "passive"))
      (node (ref "SV5") (pin "6") (pinfunction "6_6") (pintype "passive"))
    )
    (net (code "3") (name "+3V3-FPGA") (class "Default")
      (node (ref "C28") (pin "1") (pinfunction "1_1") (pintype "passive"))
      (node (ref "C32") (pin "1") (pinfunction "1_1") (pintype "passive"))
      (node (ref "C34") (pin "1") (pinfunction "1_1") (pintype "passive"))
      (node (ref "C47") (pin "1") (pinfunction "1_1") (pintype "passive"))
      (node (ref "IC1") (pin "100") (pinfunction "VCCO_B07_100") (pintype "bidirectional"))
      (node (ref "IC1") (pin "12") (pinfunction "VCCO_B76_12") (pintype "bidirectional"))
      (node (ref "IC1") (pin "26") (pinfunction "VCCO_B65_26") (pintype "bidirectional"))
      (node (ref "IC1") (pin "37") (pinfunction "VCCO_B54_37") (pintype "bidirectional"))
      (node (ref "IC1") (pin "50") (pinfunction "VCCO_B43_50") (pintype "bidirectional"))
      (node (ref "IC1") (pin "63") (pinfunction "VCCO_B32_63") (pintype "bidirectional"))
      (node (ref "IC1") (pin "76") (pinfunction "VCCO_B21_76") (pintype "bidirectional"))
      (node (ref "IC1") (pin "90") (pinfunction "VCCO_B10_90") (pintype "bidirectional"))
      (node (ref "IC13") (pin "5") (pinfunction "VO_5") (pintype "bidirectional"))
      (node (ref "IC4") (pin "5") (pinfunction "VDD_5") (pintype "bidirectional"))
      (node (ref "R59") (pin "2") (pinfunction "2_2") (pintype "passive"))
    )
    (net (code "7") (name "ADC1") (class "Default")
      (node (ref "IC1") (pin "62") (pinfunction "P62_IO3_62") (pintype "bidirectional"))
      (node (ref "IC8") (pin "3") (pinfunction "D1_3") (pintype "bidirectional"))
    )
    (net (code "8") (name "ADC2") (class "Default")
      (node (ref "IC1") (pin "60") (pinfunction "P60_IO3_60") (pintype "bidirectional"))
      (node (ref "IC8") (pin "4") (pinfunction "D2_4") (pintype "bidirectional"))
    )
    (net (code "9") (name "ADC3") (class "Default")
      (node (ref "IC1") (pin "58") (pinfunction "P58_IO3_58") (pintype "bidirectional"))
      (node (ref "IC8") (pin "5") (pinfunction "D3_5") (pintype "bidirectional"))
    )
    (net (code "10") (name "ADC4") (class "Default")
      (node (ref "IC1") (pin "57") (pinfunction "P57_IO3_57") (pintype "bidirectional"))
      (node (ref "IC8") (pin "6") (pinfunction "D4_6") (pintype "bidirectional"))
    )
    (net (code "11") (name "ADC5") (class "Default")
      (node (ref "IC1") (pin "56") (pinfunction "P56_IO3_56") (pintype "bidirectional"))
      (node (ref "IC8") (pin "7") (pinfunction "D5_7") (pintype "bidirectional"))
    )
    (net (code "12") (name "ADC6") (class "Default")
      (node (ref "IC1") (pin "55") (pinfunction "P55_IO3_55") (pintype "bidirectional"))
      (node (ref "IC8") (pin "8") (pinfunction "D6_8") (pintype "bidirectional"))
    )
    (net (code "13") (name "ADC7") (class "Default")
      (node (ref "IC1") (pin "54") (pinfunction "P54_IOV3_54") (pintype "bidirectional"))
      (node (ref "IC8") (pin "9") (pinfunction "D7_9") (pintype "bidirectional"))
    )
    (net (code "14") (name "ADC8") (class "Default")
      (node (ref "IC1") (pin "53") (pinfunction "P53_IO3_53") (pintype "bidirectional"))
      (node (ref "IC8") (pin "10") (pinfunction "MSB-D8_10") (pintype "bidirectional"))
    )
    (net (code "15") (name "ADC_CLK") (class "Default")
      (node (ref "IC1") (pin "46") (pinfunction "P46_IO4_46") (pintype "bidirectional"))
      (node (ref "IC8") (pin "12") (pinfunction "CLK_12") (pintype "bidirectional"))
    )
    (net (code "16") (name "ADC_IN") (class "Default")
      (node (ref "IC11") (pin "10") (pinfunction "B4_10") (pintype "passive"))
      (node (ref "IC11") (pin "2") (pinfunction "B1_2") (pintype "passive"))
      (node (ref "IC11") (pin "3") (pinfunction "B2_3") (pintype "passive"))
      (node (ref "IC11") (pin "9") (pinfunction "B3_9") (pintype "passive"))
      (node (ref "IC8") (pin "19") (pinfunction "ANALOGIN_19") (pintype "bidirectional"))
      (node (ref "TP1") (pin "1") (pinfunction "P$1_1") (pintype "bidirectional"))
    )
    (net (code "17") (name "ADC_NOE") (class "Default")
      (node (ref "IC1") (pin "47") (pinfunction "P47_IO4_47") (pintype "bidirectional"))
      (node (ref "IC8") (pin "1") (pinfunction "NOE_1") (pintype "bidirectional"))
      (node (ref "R47") (pin "2") (pinfunction "2_2") (pintype "passive"))
    )
    (net (code "18") (name "AMPL_HI") (class "Default")
      (node (ref "IC2") (pin "4") (pinfunction "AD5_4") (pintype "bidirectional"))
      (node (ref "R41") (pin "2") (pinfunction "2_2") (pintype "passive"))
      (node (ref "R42") (pin "2") (pinfunction "2_2") (pintype "passive"))
    )
    (net (code "19") (name "AMPL_LO") (class "Default")
      (node (ref "IC2") (pin "3") (pinfunction "AD4_3") (pintype "bidirectional"))
      (node (ref "R30") (pin "2") (pinfunction "2_2") (pintype "passive"))
      (node (ref "R31") (pin "2") (pinfunction "2_2") (pintype "passive"))
    )
    (net (code "20") (name "ANT_HI") (class "Default")
      (node (ref "C35") (pin "1") (pinfunction "1_1") (pintype "passive"))
      (node (ref "C36") (pin "1") (pinfunction "1_1") (pintype "passive"))
      (node (ref "RLY1") (pin "8") (pinfunction "COM_8") (pintype "passive"))
      (node (ref "SV2") (pin "4") (pinfunction "PIN4_4") (pintype "passive"))
      (node (ref "TP3") (pin "1") (pinfunction "P$1_1") (pintype "bidirectional"))
    )
    (net (code "21") (name "ANT_LO") (class "Default")
      (node (ref "C20") (pin "1") (pinfunction "1_1") (pintype "passive"))
      (node (ref "C39") (pin "1") (pinfunction "1_1") (pintype "passive"))
      (node (ref "RLY1") (pin "3") (pinfunction "COM_3") (pintype "passive"))
      (node (ref "SV2") (pin "2") (pinfunction "PIN2_2") (pintype "passive"))
      (node (ref "TP2") (pin "1") (pinfunction "P$1_1") (pintype "bidirectional"))
    )
    (net (code "22") (name "ARM_TCK") (class "Default")
      (node (ref "IC2") (pin "53") (pinfunction "TCK_53") (pintype "bidirectional"))
      (node (ref "R7") (pin "1") (pinfunction "1_1") (pintype "passive"))
      (node (ref "SV3") (pin "9") (pinfunction "9_9") (pintype "passive"))
    )
    (net (code "23") (name "ARM_TDI") (class "Default")
      (node (ref "IC2") (pin "33") (pinfunction "TDI_33") (pintype "bidirectional"))
      (node (ref "SV3") (pin "5") (pinfunction "5_5") (pintype "passive"))
    )
    (net (code "24") (name "ARM_TDO") (class "Default")
      (node (ref "IC2") (pin "49") (pinfunction "TDO_49") (pintype "bidirectional"))
      (node (ref "SV3") (pin "13") (pinfunction "13_13") (pintype "passive"))
    )
    (net (code "25") (name "ARM_TMS") (class "Default")
      (node (ref "IC2") (pin "51") (pinfunction "TMS_51") (pintype "bidirectional"))
      (node (ref "SV3") (pin "7") (pinfunction "7_7") (pintype "passive"))
    )
    (net (code "26") (name "BUTTON_A") (class "Default")
      (node (ref "IC2") (pin "15") (pinfunction "PA23_15") (pintype "bidirectional"))
      (node (ref "R43") (pin "1") (pinfunction "1_1") (pintype "passive"))
      (node (ref "SW1") (pin "B") (pinfunction "P$2_B") (pintype "bidirectional"))
    )
    (net (code "27") (name "CROSS_HI") (class "Default")
      (node (ref "IC5") (pin "6") (pinfunction "OUT_6") (pintype "output"))
      (node (ref "R44") (pin "1") (pinfunction "1_1") (pintype "passive"))
    )
    (net (code "28") (name "CROSS_LO") (class "Default")
      (node (ref "IC5") (pin "7") (pinfunction "OUT_7") (pintype "output"))
      (node (ref "R39") (pin "1") (pinfunction "1_1") (pintype "passive"))
    )
    (net (code "29") (name "FPGA_CCLK") (class "Default")
      (node (ref "IC1") (pin "75") (pinfunction "CCLK_75") (pintype "bidirectional"))
      (node (ref "IC2") (pin "41") (pinfunction "PA29_41") (pintype "bidirectional"))
    )
    (net (code "30") (name "FPGA_DIN") (class "Default")
      (node (ref "IC1") (pin "73") (pinfunction "DIN_73") (pintype "bidirectional"))
      (node (ref "IC2") (pin "42") (pinfunction "PA30_42") (pintype "bidirectional"))
    )
    (net (code "31") (name "FPGA_DONE") (class "Default")
      (node (ref "IC1") (pin "49") (pinfunction "DONE_49") (pintype "bidirectional"))
      (node (ref "IC2") (pin "37") (pinfunction "PA27_37") (pintype "bidirectional"))
    )
    (net (code "32") (name "FPGA_DOUT") (class "Default")
      (node (ref "IC1") (pin "74") (pinfunction "DOUT_74") (pintype "bidirectional"))
      (node (ref "IC2") (pin "52") (pinfunction "PA31_52") (pintype "bidirectional"))
    )
    (net (code "33") (name "FPGA_NINIT") (class "Default")
      (node (ref "IC1") (pin "52") (pinfunction "P52_IO3_52") (pintype "bidirectional"))
      (node (ref "IC2") (pin "36") (pinfunction "PA4_36") (pintype "bidirectional"))
      (node (ref "R59") (pin "1") (pinfunction "1_1") (pintype "passive"))
    )
    (net (code "34") (name "FPGA_NPROGRAM") (class "Default")
      (node (ref "IC1") (pin "51") (pinfunction "/PROGRAM_51") (pintype "bidirectional"))
      (node (ref "IC2") (pin "38") (pinfunction "PA28_38") (pintype "bidirectional"))
    )
    (net (code "35") (name "FPGA_ON") (class "Default")
      (node (ref "IC12") (pin "8") (pinfunction "/SHDN_8") (pintype "passive"))
      (node (ref "IC13") (pin "3") (pinfunction "VC_3") (pintype "bidirectional"))
      (node (ref "IC2") (pin "26") (pinfunction "PA26_26") (pintype "bidirectional"))
      (node (ref "R23") (pin "2") (pinfunction "2_2") (pintype "passive"))
    )
    (net (code "36") (name "FPGA_TCK") (class "Default")
      (node (ref "IC1") (pin "99") (pinfunction "TCK_99") (pintype "bidirectional"))
      (node (ref "SV5") (pin "4") (pinfunction "4_4") (pintype "passive"))
    )
    (net (code "37") (name "FPGA_TDI") (class "Default")
      (node (ref "IC1") (pin "79") (pinfunction "TDI_79") (pintype "bidirectional"))
      (node (ref "SV5") (pin "2") (pinfunction "2_2") (pintype "passive"))
    )
    (net (code "38") (name "FPGA_TDO") (class "Default")
      (node (ref "IC1") (pin "77") (pinfunction "TDO_77") (pintype "bidirectional"))
      (node (ref "SV5") (pin "3") (pinfunction "3_3") (pintype "passive"))
    )
    (net (code "39") (name "FPGA_TMS") (class "Default")
      (node (ref "IC1") (pin "2") (pinfunction "TMS_2") (pintype "bidirectional"))
      (node (ref "SV5") (pin "1") (pinfunction "1_1") (pintype "passive"))
    )
    (net (code "40") (name "GND") (class "Default")
      (node (ref "C1") (pin "2") (pinfunction "2_2") (pintype "passive"))
      (node (ref "C10") (pin "2") (pinfunction "2_2") (pintype "passive"))
      (node (ref "C11") (pin "2") (pinfunction "2_2") (pintype "passive"))
      (node (ref "C15") (pin "2") (pinfunction "2_2") (pintype "passive"))
      (node (ref "C18") (pin "2") (pinfunction "2_2") (pintype "passive"))
      (node (ref "C19") (pin "2") (pinfunction "2_2") (pintype "passive"))
      (node (ref "C2") (pin "2") (pinfunction "2_2") (pintype "passive"))
      (node (ref "C20") (pin "2") (pinfunction "2_2") (pintype "passive"))
      (node (ref "C21") (pin "2") (pinfunction "2_2") (pintype "passive"))
      (node (ref "C22") (pin "2") (pinfunction "2_2") (pintype "passive"))
      (node (ref "C23") (pin "2") (pinfunction "2_2") (pintype "passive"))
      (node (ref "C24") (pin "2") (pinfunction "2_2") (pintype "passive"))
      (node (ref "C25") (pin "2") (pinfunction "2_2") (pintype "passive"))
      (node (ref "C26") (pin "2") (pinfunction "2_2") (pintype "passive"))
      (node (ref "C27") (pin "2") (pinfunction "2_2") (pintype "passive"))
      (node (ref "C28") (pin "2") (pinfunction "2_2") (pintype "passive"))
      (node (ref "C29") (pin "2") (pinfunction "2_2") (pintype "passive"))
      (node (ref "C3") (pin "2") (pinfunction "2_2") (pintype "passive"))
      (node (ref "C30") (pin "2") (pinfunction "2_2") (pintype "passive"))
      (node (ref "C31") (pin "2") (pinfunction "2_2") (pintype "passive"))
      (node (ref "C32") (pin "2") (pinfunction "2_2") (pintype "passive"))
      (node (ref "C33") (pin "2") (pinfunction "2_2") (pintype "passive"))
      (node (ref "C34") (pin "2") (pinfunction "2_2") (pintype "passive"))
      (node (ref "C35") (pin "2") (pinfunction "2_2") (pintype "passive"))
      (node (ref "C36") (pin "2") (pinfunction "2_2") (pintype "passive"))
      (node (ref "C37") (pin "-") (pinfunction "-_-") (pintype "passive"))
      (node (ref "C38") (pin "-") (pinfunction "-_-") (pintype "passive"))
      (node (ref "C39") (pin "2") (pinfunction "2_2") (pintype "passive"))
      (node (ref "C4") (pin "1") (pinfunction "1_1") (pintype "passive"))
      (node (ref "C44") (pin "2") (pinfunction "2_2") (pintype "passive"))
      (node (ref "C45") (pin "2") (pinfunction "2_2") (pintype "passive"))
      (node (ref "C46") (pin "2") (pinfunction "2_2") (pintype "passive"))
      (node (ref "C47") (pin "2") (pinfunction "2_2") (pintype "passive"))
      (node (ref "C5") (pin "1") (pinfunction "1_1") (pintype "passive"))
      (node (ref "C6") (pin "1") (pinfunction "1_1") (pintype "passive"))
      (node (ref "C7") (pin "1") (pinfunction "1_1") (pintype "passive"))
      (node (ref "C8") (pin "2") (pinfunction "2_2") (pintype "passive"))
      (node (ref "C9") (pin "2") (pinfunction "2_2") (pintype "passive"))
      (node (ref "D10") (pin "1") (pinfunction "A_1") (pintype "passive"))
      (node (ref "D11") (pin "1") (pinfunction "A_1") (pintype "passive"))
      (node (ref "D3") (pin "1") (pinfunction "A_1") (pintype "passive"))
      (node (ref "D4") (pin "-") (pinfunction "C_-") (pintype "passive"))
      (node (ref "D5") (pin "-") (pinfunction "C_-") (pintype "passive"))
      (node (ref "D6") (pin "-") (pinfunction "C_-") (pintype "passive"))
      (node (ref "D8") (pin "3") (pinfunction "A_3") (pintype "bidirectional"))
      (node (ref "D9") (pin "-") (pinfunction "C_-") (pintype "passive"))
      (node (ref "IC1") (pin "1") (pinfunction "GND1_1") (pintype "bidirectional"))
      (node (ref "IC1") (pin "11") (pinfunction "GND2_11") (pintype "bidirectional"))
      (node (ref "IC1") (pin "24") (pinfunction "GND8_24") (pintype "bidirectional"))
      (node (ref "IC1") (pin "28") (pinfunction "NC0_28") (pintype "bidirectional"))
      (node (ref "IC1") (pin "29") (pinfunction "NC1_29") (pintype "bidirectional"))
      (node (ref "IC1") (pin "38") (pinfunction "GND3_38") (pintype "bidirectional"))
      (node (ref "IC1") (pin "48") (pinfunction "GND6_48") (pintype "bidirectional"))
      (node (ref "IC1") (pin "64") (pinfunction "GND7_64") (pintype "bidirectional"))
      (node (ref "IC1") (pin "78") (pinfunction "GND4_78") (pintype "bidirectional"))
      (node (ref "IC1") (pin "89") (pinfunction "GND5_89") (pintype "bidirectional"))
      (node (ref "IC10") (pin "10") (pinfunction "VSS_10") (pintype "bidirectional"))
      (node (ref "IC11") (pin "7") (pinfunction "VSS_7") (pintype "bidirectional"))
      (node (ref "IC12") (pin "3") (pinfunction "GND_3") (pintype "passive"))
      (node (ref "IC13") (pin "2") (pinfunction "GND_2") (pintype "bidirectional"))
      (node (ref "IC14") (pin "4") (pinfunction "V-_4") (pintype "bidirectional"))
      (node (ref "IC2") (pin "17") (pinfunction "GND1_17") (pintype "bidirectional"))
      (node (ref "IC2") (pin "2") (pinfunction "GND0_2") (pintype "bidirectional"))
      (node (ref "IC2") (pin "46") (pinfunction "GND2_46") (pintype "bidirectional"))
      (node (ref "IC2") (pin "60") (pinfunction "GND3_60") (pintype "bidirectional"))
      (node (ref "IC3") (pin "2") (pinfunction "GND_2") (pintype "bidirectional"))
      (node (ref "IC4") (pin "3") (pinfunction "VSS_3") (pintype "bidirectional"))
      (node (ref "IC5") (pin "2") (pinfunction "-IN_2") (pintype "input"))
      (node (ref "IC5") (pin "4") (pinfunction "-IN_4") (pintype "input"))
      (node (ref "IC5") (pin "5") (pinfunction "V-_5") (pintype "bidirectional"))
      (node (ref "IC6") (pin "11") (pinfunction "V-_11") (pintype "bidirectional"))
      (node (ref "IC6") (pin "12") (pinfunction "+IN_12") (pintype "input"))
      (node (ref "IC6") (pin "13") (pinfunction "-IN_13") (pintype "input"))
      (node (ref "IC7") (pin "3") (pinfunction "V-_3") (pintype "bidirectional"))
      (node (ref "IC8") (pin "2") (pinfunction "DGND0_2") (pintype "bidirectional"))
      (node (ref "IC8") (pin "20") (pinfunction "AGND0_20") (pintype "bidirectional"))
      (node (ref "IC8") (pin "21") (pinfunction "AGND1_21") (pintype "bidirectional"))
      (node (ref "IC8") (pin "24") (pinfunction "DGND1_24") (pintype "bidirectional"))
      (node (ref "IC9") (pin "10") (pinfunction "VSS_10") (pintype "bidirectional"))
      (node (ref "Q1") (pin "2") (pinfunction "E_2") (pintype "bidirectional"))
      (node (ref "Q2") (pin "1") (pinfunction "S_1") (pintype "passive"))
      (node (ref "Q2") (pin "2") (pinfunction "G_2") (pintype "passive"))
      (node (ref "Q2") (pin "8") (pinfunction "D_8") (pintype "passive"))
      (node (ref "R10") (pin "1") (pinfunction "1_1") (pintype "passive"))
      (node (ref "R11") (pin "1") (pinfunction "1_1") (pintype "passive"))
      (node (ref "R15") (pin "1") (pinfunction "1_1") (pintype "passive"))
      (node (ref "R23") (pin "1") (pinfunction "1_1") (pintype "passive"))
      (node (ref "R31") (pin "1") (pinfunction "1_1") (pintype "passive"))
      (node (ref "R42") (pin "1") (pinfunction "1_1") (pintype "passive"))
      (node (ref "R54") (pin "1") (pinfunction "1_1") (pintype "passive"))
      (node (ref "SV1") (pin "5") (pinfunction "GND/5_5") (pintype "bidirectional"))
      (node (ref "SV1") (pin "TAB0") (pinfunction "SHLD0_TAB0") (pintype "bidirectional"))
      (node (ref "SV1") (pin "TAB1") (pinfunction "SHLD1_TAB1") (pintype "bidirectional"))
      (node (ref "SV1") (pin "TAB2") (pinfunction "SHLD2_TAB2") (pintype "bidirectional"))
      (node (ref "SV1") (pin "TAB3") (pinfunction "SHLD3_TAB3") (pintype "bidirectional"))
      (node (ref "SV3") (pin "10") (pinfunction "10_10") (pintype "passive"))
      (node (ref "SV3") (pin "12") (pinfunction "12_12") (pintype "passive"))
      (node (ref "SV3") (pin "14") (pinfunction "14_14") (pintype "passive"))
      (node (ref "SV3") (pin "16") (pinfunction "16_16") (pintype "passive"))
      (node (ref "SV3") (pin "18") (pinfunction "18_18") (pintype "passive"))
      (node (ref "SV3") (pin "20") (pinfunction "20_20") (pintype "passive"))
      (node (ref "SV3") (pin "4") (pinfunction "4_4") (pintype "passive"))
      (node (ref "SV3") (pin "6") (pinfunction "6_6") (pintype "passive"))
      (node (ref "SV3") (pin "8") (pinfunction "8_8") (pintype "passive"))
      (node (ref "SV5") (pin "5") (pinfunction "5_5") (pintype "passive"))
      (node (ref "SW1") (pin "A") (pinfunction "P$1_A") (pintype "bidirectional"))
      (node (ref "TP6") (pin "A") (pinfunction "P$1_A") (pintype "bidirectional"))
    )
    (net (code "41") (name "LED_A") (class "Default")
      (node (ref "IC2") (pin "48") (pinfunction "PA0_48") (pintype "bidirectional"))
      (node (ref "R24") (pin "1") (pinfunction "1_1") (pintype "passive"))
    )
    (net (code "42") (name "LED_B") (class "Default")
      (node (ref "IC2") (pin "31") (pinfunction "PA8_31") (pintype "bidirectional"))
      (node (ref "R25") (pin "1") (pinfunction "1_1") (pintype "passive"))
    )
    (net (code "43") (name "LED_C") (class "Default")
      (node (ref "IC2") (pin "30") (pinfunction "PA9_30") (pintype "bidirectional"))
      (node (ref "R26") (pin "1") (pinfunction "1_1") (pintype "passive"))
    )
    (net (code "44") (name "LED_D") (class "Default")
      (node (ref "IC2") (pin "44") (pinfunction "PA2_44") (pintype "bidirectional"))
      (node (ref "R55") (pin "1") (pinfunction "1_1") (pintype "passive"))
      (node (ref "TP8") (pin "1") (pinfunction "P$1_1") (pintype "bidirectional"))
    )
    (net (code "45") (name "MISO") (class "Default")
      (node (ref "IC1") (pin "40") (pinfunction "P40_IO4_40") (pintype "bidirectional"))
      (node (ref "IC2") (pin "27") (pinfunction "PA12_27") (pintype "bidirectional"))
    )
    (net (code "46") (name "MOSI") (class "Default")
      (node (ref "IC1") (pin "43") (pinfunction "P43_IO4_43") (pintype "bidirectional"))
      (node (ref "IC2") (pin "22") (pinfunction "PA13_22") (pintype "bidirectional"))
    )
    (net (code "47") (name "MUXSEL_HIPKD") (class "Default")
      (node (ref "IC11") (pin "12") (pinfunction "C4_12") (pintype "input"))
      (node (ref "IC2") (pin "13") (pinfunction "PA19/AD2_13") (pintype "bidirectional"))
    )
    (net (code "48") (name "MUXSEL_HIRAW") (class "Default")
      (node (ref "IC11") (pin "6") (pinfunction "C3_6") (pintype "input"))
      (node (ref "IC2") (pin "11") (pinfunction "PA21_11") (pintype "bidirectional"))
    )
    (net (code "49") (name "MUXSEL_LOPKD") (class "Default")
      (node (ref "IC11") (pin "5") (pinfunction "C2_5") (pintype "input"))
      (node (ref "IC2") (pin "16") (pinfunction "PA20/AD3_16") (pintype "bidirectional"))
    )
    (net (code "50") (name "MUXSEL_LORAW") (class "Default")
      (node (ref "IC11") (pin "13") (pinfunction "C1_13") (pintype "input"))
      (node (ref "IC2") (pin "14") (pinfunction "PA22_14") (pintype "bidirectional"))
    )
    (net (code "51") (name "NCS") (class "Default")
      (node (ref "IC1") (pin "44") (pinfunction "P44_IO4_44") (pintype "bidirectional"))
      (node (ref "IC2") (pin "28") (pinfunction "PA11_28") (pintype "bidirectional"))
    )
    (net (code "52") (name "NVDD_ON") (class "Default")
      (node (ref "IC2") (pin "43") (pinfunction "PA3_43") (pintype "bidirectional"))
      (node (ref "R57") (pin "1") (pinfunction "1_1") (pintype "passive"))
    )
    (net (code "53") (name "Net-(C4-Pad2)") (class "Default")
      (node (ref "C4") (pin "2") (pinfunction "2_2") (pintype "passive"))
      (node (ref "R3") (pin "1") (pinfunction "1_1") (pintype "passive"))
    )
    (net (code "54") (name "Net-(C16-Pad1)") (class "Default")
      (node (ref "C16") (pin "1") (pinfunction "1_1") (pintype "passive"))
      (node (ref "R16") (pin "2") (pinfunction "2_2") (pintype "passive"))
    )
    (net (code "55") (name "Net-(C42-Pad2)") (class "Default")
      (node (ref "C42") (pin "2") (pinfunction "2_2") (pintype "passive"))
      (node (ref "R35") (pin "1") (pinfunction "1_1") (pintype "passive"))
    )
    (net (code "56") (name "Net-(C43-Pad2)") (class "Default")
      (node (ref "C43") (pin "2") (pinfunction "2_2") (pintype "passive"))
      (node (ref "R32") (pin "1") (pinfunction "1_1") (pintype "passive"))
    )
    (net (code "57") (name "Net-(D1-A)") (class "Default")
      (node (ref "D1") (pin "1") (pinfunction "A_1") (pintype "passive"))
      (node (ref "R20") (pin "1") (pinfunction "1_1") (pintype "passive"))
      (node (ref "RLY1") (pin "2") (pinfunction "NC_2") (pintype "passive"))
    )
    (net (code "58") (name "Net-(D1-C)") (class "Default")
      (node (ref "C11") (pin "1") (pinfunction "1_1") (pintype "passive"))
      (node (ref "C12") (pin "1") (pinfunction "1_1") (pintype "passive"))
      (node (ref "D1") (pin "3") (pinfunction "C_3") (pintype "passive"))
      (node (ref "D11") (pin "3") (pinfunction "C_3") (pintype "passive"))
      (node (ref "R11") (pin "2") (pinfunction "2_2") (pintype "passive"))
      (node (ref "R30") (pin "1") (pinfunction "1_1") (pintype "passive"))
    )
    (net (code "59") (name "Net-(D2-A)") (class "Default")
      (node (ref "C14") (pin "2") (pinfunction "2_2") (pintype "passive"))
      (node (ref "D2") (pin "1") (pinfunction "A_1") (pintype "passive"))
      (node (ref "D3") (pin "3") (pinfunction "C_3") (pintype "passive"))
    )
    (net (code "60") (name "Net-(D4-A)") (class "Default")
      (node (ref "D4") (pin "+") (pinfunction "A_+") (pintype "passive"))
      (node (ref "R24") (pin "2") (pinfunction "2_2") (pintype "passive"))
    )
    (net (code "61") (name "Net-(D5-A)") (class "Default")
      (node (ref "D5") (pin "+") (pinfunction "A_+") (pintype "passive"))
      (node (ref "R25") (pin "2") (pinfunction "2_2") (pintype "passive"))
    )
    (net (code "62") (name "Net-(D6-A)") (class "Default")
      (node (ref "D6") (pin "+") (pinfunction "A_+") (pintype "passive"))
      (node (ref "R26") (pin "2") (pinfunction "2_2") (pintype "passive"))
    )
    (net (code "63") (name "Net-(D7-A)") (class "Default")
      (node (ref "D7") (pin "1") (pinfunction "A_1") (pintype "passive"))
      (node (ref "Q1") (pin "3") (pinfunction "C_3") (pintype "bidirectional"))
      (node (ref "RLY1") (pin "10") (pinfunction "P$2_10") (pintype "passive"))
    )
    (net (code "64") (name "Net-(D9-A)") (class "Default")
      (node (ref "D9") (pin "+") (pinfunction "A_+") (pintype "passive"))
      (node (ref "R55") (pin "2") (pinfunction "2_2") (pintype "passive"))
    )
    (net (code "65") (name "Net-(D10-C)") (class "Default")
      (node (ref "C15") (pin "1") (pinfunction "1_1") (pintype "passive"))
      (node (ref "D10") (pin "3") (pinfunction "C_3") (pintype "passive"))
      (node (ref "D2") (pin "3") (pinfunction "C_3") (pintype "passive"))
      (node (ref "R15") (pin "2") (pinfunction "2_2") (pintype "passive"))
      (node (ref "R16") (pin "1") (pinfunction "1_1") (pintype "passive"))
      (node (ref "R41") (pin "1") (pinfunction "1_1") (pintype "passive"))
    )
    (net (code "66") (name "Net-(IC1-P22_IO6)") (class "Default")
      (node (ref "IC1") (pin "22") (pinfunction "P22_IO6_22") (pintype "bidirectional"))
      (node (ref "TP7") (pin "1") (pinfunction "P$1_1") (pintype "bidirectional"))
    )
    (net (code "67") (name "Net-(IC1-P87_IO1)") (class "Default")
      (node (ref "IC1") (pin "87") (pinfunction "P87_IO1_87") (pintype "bidirectional"))
      (node (ref "R39") (pin "2") (pinfunction "2_2") (pintype "passive"))
    )
    (net (code "68") (name "Net-(IC1-P88_IGCK1)") (class "Default")
      (node (ref "IC1") (pin "88") (pinfunction "P88_IGCK1_88") (pintype "bidirectional"))
      (node (ref "R44") (pin "2") (pinfunction "2_2") (pintype "passive"))
    )
    (net (code "69") (name "Net-(IC1-P91_IGCK0)") (class "Default")
      (node (ref "C3") (pin "1") (pinfunction "1_1") (pintype "passive"))
      (node (ref "IC1") (pin "91") (pinfunction "P91_IGCK0_91") (pintype "bidirectional"))
      (node (ref "IC1") (pin "93") (pinfunction "P93_IOV0_93") (pintype "bidirectional"))
      (node (ref "R1") (pin "2") (pinfunction "2_2") (pintype "passive"))
      (node (ref "R2") (pin "2") (pinfunction "2_2") (pintype "passive"))
      (node (ref "XT1") (pin "B") (pinfunction "B_B") (pintype "bidirectional"))
    )
    (net (code "70") (name "Net-(IC2-DDM)") (class "Default")
      (node (ref "IC2") (pin "56") (pinfunction "DDM_56") (pintype "bidirectional"))
      (node (ref "R4") (pin "2") (pinfunction "2_2") (pintype "passive"))
    )
    (net (code "71") (name "Net-(IC2-DDP)") (class "Default")
      (node (ref "IC2") (pin "57") (pinfunction "DDP_57") (pintype "bidirectional"))
      (node (ref "R5") (pin "2") (pinfunction "2_2") (pintype "passive"))
      (node (ref "R6") (pin "1") (pinfunction "1_1") (pintype "passive"))
    )
    (net (code "72") (name "Net-(IC2-NRST)") (class "Default")
      (node (ref "IC2") (pin "39") (pinfunction "NRST_39") (pintype "bidirectional"))
      (node (ref "R8") (pin "2") (pinfunction "2_2") (pintype "passive"))
    )
    (net (code "73") (name "Net-(IC2-PLLRC)") (class "Default")
      (node (ref "C5") (pin "2") (pinfunction "2_2") (pintype "passive"))
      (node (ref "IC2") (pin "63") (pinfunction "PLLRC_63") (pintype "bidirectional"))
      (node (ref "R3") (pin "2") (pinfunction "2_2") (pintype "passive"))
    )
    (net (code "74") (name "Net-(IC2-VDDCORE0)") (class "Default")
      (node (ref "C8") (pin "1") (pinfunction "1_1") (pintype "passive"))
      (node (ref "C9") (pin "1") (pinfunction "1_1") (pintype "passive"))
      (node (ref "IC2") (pin "12") (pinfunction "VDDCORE0_12") (pintype "bidirectional"))
      (node (ref "IC2") (pin "24") (pinfunction "VDDCORE1_24") (pintype "bidirectional"))
      (node (ref "IC2") (pin "54") (pinfunction "VDDCORE2_54") (pintype "bidirectional"))
      (node (ref "IC2") (pin "64") (pinfunction "VDDPLL_64") (pintype "bidirectional"))
      (node (ref "IC2") (pin "8") (pinfunction "VDDOUT_8") (pintype "bidirectional"))
    )
    (net (code "75") (name "Net-(IC2-XIN{slash}PGMCK)") (class "Default")
      (node (ref "C7") (pin "2") (pinfunction "2_2") (pintype "passive"))
      (node (ref "IC2") (pin "62") (pinfunction "XIN/PGMCK_62") (pintype "bidirectional"))
      (node (ref "XT2") (pin "A") (pinfunction "A_A") (pintype "bidirectional"))
    )
    (net (code "76") (name "Net-(IC2-XOUT)") (class "Default")
      (node (ref "C6") (pin "2") (pinfunction "2_2") (pintype "passive"))
      (node (ref "IC2") (pin "61") (pinfunction "XOUT_61") (pintype "bidirectional"))
      (node (ref "XT2") (pin "B") (pinfunction "B_B") (pintype "bidirectional"))
    )
    (net (code "77") (name "Net-(IC3-VC)") (class "Default")
      (node (ref "IC3") (pin "1") (pinfunction "VIN_1") (pintype "bidirectional"))
      (node (ref "IC3") (pin "3") (pinfunction "VC_3") (pintype "bidirectional"))
      (node (ref "Q2") (pin "3") (pinfunction "S_3") (pintype "passive"))
      (node (ref "R56") (pin "2") (pinfunction "2_2") (pintype "passive"))
      (node (ref "R58") (pin "2") (pinfunction "2_2") (pintype "passive"))
      (node (ref "U1") (pin "2") (pinfunction "B_2") (pintype "bidirectional"))
    )
    (net (code "78") (name "Net-(IC4-A)") (class "Default")
      (node (ref "C2") (pin "1") (pinfunction "1_1") (pintype "passive"))
      (node (ref "IC4") (pin "2") (pinfunction "A_2") (pintype "bidirectional"))
      (node (ref "R1") (pin "1") (pinfunction "1_1") (pintype "passive"))
      (node (ref "XT1") (pin "A") (pinfunction "A_A") (pintype "bidirectional"))
    )
    (net (code "79") (name "Net-(IC4-Y)") (class "Default")
      (node (ref "IC4") (pin "4") (pinfunction "Y_4") (pintype "bidirectional"))
      (node (ref "R2") (pin "1") (pinfunction "1_1") (pintype "passive"))
    )
    (net (code "80") (name "Net-(IC5A-+IN)") (class "Default")
      (node (ref "IC5") (pin "1") (pinfunction "+IN_1") (pintype "input"))
      (node (ref "R20") (pin "2") (pinfunction "2_2") (pintype "passive"))
    )
    (net (code "81") (name "Net-(IC5B-+IN)") (class "Default")
      (node (ref "IC5") (pin "3") (pinfunction "+IN_3") (pintype "input"))
      (node (ref "R21") (pin "2") (pinfunction "2_2") (pintype "passive"))
    )
    (net (code "82") (name "Net-(IC6A-+IN)") (class "Default")
      (node (ref "IC6") (pin "3") (pinfunction "+IN_3") (pintype "input"))
      (node (ref "R10") (pin "2") (pinfunction "2_2") (pintype "passive"))
      (node (ref "R9") (pin "1") (pinfunction "1_1") (pintype "passive"))
    )
    (net (code "83") (name "Net-(IC6B-+IN)") (class "Default")
      (node (ref "C12") (pin "2") (pinfunction "2_2") (pintype "passive"))
      (node (ref "IC6") (pin "5") (pinfunction "+IN_5") (pintype "input"))
      (node (ref "R12") (pin "2") (pinfunction "2_2") (pintype "passive"))
    )
    (net (code "84") (name "Net-(IC6B--IN)") (class "Default")
      (node (ref "C13") (pin "1") (pinfunction "1_1") (pintype "passive"))
      (node (ref "IC6") (pin "6") (pinfunction "-IN_6") (pintype "input"))
      (node (ref "R13") (pin "2") (pinfunction "2_2") (pintype "passive"))
      (node (ref "R14") (pin "1") (pinfunction "1_1") (pintype "passive"))
    )
    (net (code "85") (name "Net-(IC6C-+IN)") (class "Default")
      (node (ref "C16") (pin "2") (pinfunction "2_2") (pintype "passive"))
      (node (ref "IC6") (pin "10") (pinfunction "+IN_10") (pintype "input"))
      (node (ref "R17") (pin "2") (pinfunction "2_2") (pintype "passive"))
      (node (ref "R36") (pin "2") (pinfunction "2_2") (pintype "passive"))
      (node (ref "R37") (pin "2") (pinfunction "2_2") (pintype "passive"))
    )
    (net (code "86") (name "Net-(IC6C--IN)") (class "Default")
      (node (ref "C17") (pin "1") (pinfunction "1_1") (pintype "passive"))
      (node (ref "IC6") (pin "9") (pinfunction "-IN_9") (pintype "input"))
      (node (ref "R18") (pin "1") (pinfunction "1_1") (pintype "passive"))
      (node (ref "R19") (pin "2") (pinfunction "2_2") (pintype "passive"))
    )
    (net (code "87") (name "Net-(IC7-OUT)") (class "Default")
      (node (ref "IC7") (pin "1") (pinfunction "OUT_1") (pintype "bidirectional"))
      (node (ref "R8") (pin "1") (pinfunction "1_1") (pintype "passive"))
    )
    (net (code "88") (name "Net-(IC8-REFB)") (class "Default")
      (node (ref "C18") (pin "1") (pinfunction "1_1") (pintype "passive"))
      (node (ref "IC8") (pin "23") (pinfunction "REFB_23") (pintype "bidirectional"))
      (node (ref "R53") (pin "1") (pinfunction "1_1") (pintype "passive"))
      (node (ref "R54") (pin "2") (pinfunction "2_2") (pintype "passive"))
    )
    (net (code "89") (name "Net-(IC8-REFT)") (class "Default")
      (node (ref "C19") (pin "1") (pinfunction "1_1") (pintype "passive"))
      (node (ref "IC8") (pin "17") (pinfunction "REFT_17") (pintype "bidirectional"))
      (node (ref "R52") (pin "1") (pinfunction "1_1") (pintype "passive"))
      (node (ref "R53") (pin "2") (pinfunction "2_2") (pintype "passive"))
    )
    (net (code "90") (name "Net-(IC9-1Y1)") (class "Default")
      (node (ref "IC9") (pin "12") (pinfunction "1Y4_12") (pintype "bidirectional"))
      (node (ref "IC9") (pin "14") (pinfunction "1Y3_14") (pintype "bidirectional"))
      (node (ref "IC9") (pin "16") (pinfunction "1Y2_16") (pintype "bidirectional"))
      (node (ref "IC9") (pin "18") (pinfunction "1Y1_18") (pintype "bidirectional"))
      (node (ref "R27") (pin "1") (pinfunction "1_1") (pintype "passive"))
    )
    (net (code "91") (name "Net-(IC9-2Y1)") (class "Default")
      (node (ref "IC9") (pin "9") (pinfunction "2Y1_9") (pintype "bidirectional"))
      (node (ref "R45") (pin "1") (pinfunction "1_1") (pintype "passive"))
    )
    (net (code "92") (name "Net-(IC9-2Y2)") (class "Default")
      (node (ref "IC9") (pin "3") (pinfunction "2Y4_3") (pintype "bidirectional"))
      (node (ref "IC9") (pin "5") (pinfunction "2Y3_5") (pintype "bidirectional"))
      (node (ref "IC9") (pin "7") (pinfunction "2Y2_7") (pintype "bidirectional"))
      (node (ref "R22") (pin "1") (pinfunction "1_1") (pintype "passive"))
    )
    (net (code "93") (name "Net-(IC10-1Y1)") (class "Default")
      (node (ref "IC10") (pin "12") (pinfunction "1Y4_12") (pintype "bidirectional"))
      (node (ref "IC10") (pin "14") (pinfunction "1Y3_14") (pintype "bidirectional"))
      (node (ref "IC10") (pin "16") (pinfunction "1Y2_16") (pintype "bidirectional"))
      (node (ref "IC10") (pin "18") (pinfunction "1Y1_18") (pintype "bidirectional"))
      (node (ref "R28") (pin "1") (pinfunction "1_1") (pintype "passive"))
    )
    (net (code "94") (name "Net-(IC10-2Y1)") (class "Default")
      (node (ref "IC10") (pin "9") (pinfunction "2Y1_9") (pintype "bidirectional"))
      (node (ref "R46") (pin "1") (pinfunction "1_1") (pintype "passive"))
    )
    (net (code "95") (name "Net-(IC10-2Y2)") (class "Default")
      (node (ref "IC10") (pin "3") (pinfunction "2Y4_3") (pintype "bidirectional"))
      (node (ref "IC10") (pin "5") (pinfunction "2Y3_5") (pintype "bidirectional"))
      (node (ref "IC10") (pin "7") (pinfunction "2Y2_7") (pintype "bidirectional"))
      (node (ref "R29") (pin "1") (pinfunction "1_1") (pintype "passive"))
    )
    (net (code "96") (name "Net-(IC11-A1)") (class "Default")
      (node (ref "C41") (pin "2") (pinfunction "2_2") (pintype "passive"))
      (node (ref "IC11") (pin "1") (pinfunction "A1_1") (pintype "passive"))
      (node (ref "IC14") (pin "7") (pinfunction "OUT_7") (pintype "output"))
      (node (ref "R34") (pin "2") (pinfunction "2_2") (pintype "passive"))
    )
    (net (code "97") (name "Net-(IC11-A2)") (class "Default")
      (node (ref "C13") (pin "2") (pinfunction "2_2") (pintype "passive"))
      (node (ref "IC11") (pin "4") (pinfunction "A2_4") (pintype "passive"))
      (node (ref "IC6") (pin "7") (pinfunction "OUT_7") (pintype "output"))
      (node (ref "R14") (pin "2") (pinfunction "2_2") (pintype "passive"))
    )
    (net (code "98") (name "Net-(IC11-A3)") (class "Default")
      (node (ref "C40") (pin "2") (pinfunction "2_2") (pintype "passive"))
      (node (ref "IC11") (pin "8") (pinfunction "A3_8") (pintype "passive"))
      (node (ref "IC14") (pin "1") (pinfunction "OUT_1") (pintype "output"))
      (node (ref "R33") (pin "2") (pinfunction "2_2") (pintype "passive"))
    )
    (net (code "99") (name "Net-(IC11-A4)") (class "Default")
      (node (ref "C17") (pin "2") (pinfunction "2_2") (pintype "passive"))
      (node (ref "IC11") (pin "11") (pinfunction "A4_11") (pintype "passive"))
      (node (ref "IC6") (pin "8") (pinfunction "OUT_8") (pintype "output"))
      (node (ref "R18") (pin "2") (pinfunction "2_2") (pintype "passive"))
    )
    (net (code "100") (name "Net-(IC14A-+IN)") (class "Default")
      (node (ref "IC14") (pin "3") (pinfunction "+IN_3") (pintype "input"))
      (node (ref "R35") (pin "2") (pinfunction "2_2") (pintype "passive"))
      (node (ref "R49") (pin "2") (pinfunction "2_2") (pintype "passive"))
    )
    (net (code "101") (name "Net-(IC14A--IN)") (class "Default")
      (node (ref "C40") (pin "1") (pinfunction "1_1") (pintype "passive"))
      (node (ref "IC14") (pin "2") (pinfunction "-IN_2") (pintype "input"))
      (node (ref "R33") (pin "1") (pinfunction "1_1") (pintype "passive"))
      (node (ref "R51") (pin "2") (pinfunction "2_2") (pintype "passive"))
    )
    (net (code "102") (name "Net-(IC14B-+IN)") (class "Default")
      (node (ref "IC14") (pin "5") (pinfunction "+IN_5") (pintype "input"))
      (node (ref "R32") (pin "2") (pinfunction "2_2") (pintype "passive"))
      (node (ref "R48") (pin "2") (pinfunction "2_2") (pintype "passive"))
    )
    (net (code "103") (name "Net-(IC14B--IN)") (class "Default")
      (node (ref "C41") (pin "1") (pinfunction "1_1") (pintype "passive"))
      (node (ref "IC14") (pin "6") (pinfunction "-IN_6") (pintype "input"))
      (node (ref "R34") (pin "1") (pinfunction "1_1") (pintype "passive"))
      (node (ref "R50") (pin "2") (pinfunction "2_2") (pintype "passive"))
    )
    (net (code "104") (name "Net-(Q1-B)") (class "Default")
      (node (ref "Q1") (pin "1") (pinfunction "B_1") (pintype "bidirectional"))
      (node (ref "R40") (pin "2") (pinfunction "2_2") (pintype "passive"))
    )
    (net (code "105") (name "Net-(Q2B-G)") (class "Default")
      (node (ref "Q2") (pin "4") (pinfunction "G_4") (pintype "passive"))
      (node (ref "R56") (pin "1") (pinfunction "1_1") (pintype "passive"))
      (node (ref "R57") (pin "2") (pinfunction "2_2") (pintype "passive"))
    )
    (net (code "106") (name "Net-(R37-Pad1)") (class "Default")
      (node (ref "R37") (pin "1") (pinfunction "1_1") (pintype "passive"))
      (node (ref "R38") (pin "2") (pinfunction "2_2") (pintype "passive"))
    )
    (net (code "107") (name "Net-(RLY1A-NC)") (class "Default")
      (node (ref "C14") (pin "1") (pinfunction "1_1") (pintype "passive"))
      (node (ref "R21") (pin "1") (pinfunction "1_1") (pintype "passive"))
      (node (ref "RLY1") (pin "9") (pinfunction "NC_9") (pintype "passive"))
    )
    (net (code "108") (name "Net-(RLY1A-NO)") (class "Default")
      (node (ref "C42") (pin "1") (pinfunction "1_1") (pintype "passive"))
      (node (ref "RLY1") (pin "7") (pinfunction "NO_7") (pintype "passive"))
    )
    (net (code "109") (name "Net-(RLY1B-NO)") (class "Default")
      (node (ref "C43") (pin "1") (pinfunction "1_1") (pintype "passive"))
      (node (ref "RLY1") (pin "4") (pinfunction "NO_4") (pintype "passive"))
    )
    (net (code "110") (name "Net-(SV1-VBUS{slash}1)") (class "Default")
      (node (ref "C1") (pin "1") (pinfunction "1_1") (pintype "passive"))
      (node (ref "SV1") (pin "1") (pinfunction "VBUS/1_1") (pintype "bidirectional"))
      (node (ref "U1") (pin "1") (pinfunction "A_1") (pintype "bidirectional"))
    )
    (net (code "111") (name "Net-(SV2-PIN1)") (class "Default")
      (node (ref "R22") (pin "2") (pinfunction "2_2") (pintype "passive"))
      (node (ref "R28") (pin "2") (pinfunction "2_2") (pintype "passive"))
      (node (ref "R46") (pin "2") (pinfunction "2_2") (pintype "passive"))
      (node (ref "SV2") (pin "1") (pinfunction "PIN1_1") (pintype "passive"))
      (node (ref "TP5") (pin "1") (pinfunction "P$1_1") (pintype "bidirectional"))
    )
    (net (code "112") (name "Net-(SV2-PIN3)") (class "Default")
      (node (ref "R27") (pin "2") (pinfunction "2_2") (pintype "passive"))
      (node (ref "R29") (pin "2") (pinfunction "2_2") (pintype "passive"))
      (node (ref "R45") (pin "2") (pinfunction "2_2") (pintype "passive"))
      (node (ref "SV2") (pin "3") (pinfunction "PIN3_3") (pintype "passive"))
      (node (ref "TP4") (pin "1") (pinfunction "P$1_1") (pintype "bidirectional"))
    )
    (net (code "113") (name "PCK0") (class "Default")
      (node (ref "IC1") (pin "36") (pinfunction "P36_IGCK5_36") (pintype "bidirectional"))
      (node (ref "IC2") (pin "34") (pinfunction "PA6_34") (pintype "bidirectional"))
    )
    (net (code "114") (name "PWR_HI") (class "Default")
      (node (ref "IC1") (pin "80") (pinfunction "P80_IO1_80") (pintype "bidirectional"))
      (node (ref "IC10") (pin "13") (pinfunction "2A2_13") (pintype "bidirectional"))
      (node (ref "IC10") (pin "15") (pinfunction "2A3_15") (pintype "bidirectional"))
      (node (ref "IC10") (pin "17") (pinfunction "2A4_17") (pintype "bidirectional"))
      (node (ref "IC9") (pin "11") (pinfunction "2A1_11") (pintype "bidirectional"))
      (node (ref "IC9") (pin "2") (pinfunction "1A1_2") (pintype "bidirectional"))
      (node (ref "IC9") (pin "4") (pinfunction "1A2_4") (pintype "bidirectional"))
      (node (ref "IC9") (pin "6") (pinfunction "1A3_6") (pintype "bidirectional"))
      (node (ref "IC9") (pin "8") (pinfunction "1A4_8") (pintype "bidirectional"))
    )
    (net (code "115") (name "PWR_LO") (class "Default")
      (node (ref "IC1") (pin "81") (pinfunction "P81_IO1_81") (pintype "bidirectional"))
      (node (ref "IC10") (pin "11") (pinfunction "2A1_11") (pintype "bidirectional"))
      (node (ref "IC10") (pin "2") (pinfunction "1A1_2") (pintype "bidirectional"))
      (node (ref "IC10") (pin "4") (pinfunction "1A2_4") (pintype "bidirectional"))
      (node (ref "IC10") (pin "6") (pinfunction "1A3_6") (pintype "bidirectional"))
      (node (ref "IC10") (pin "8") (pinfunction "1A4_8") (pintype "bidirectional"))
      (node (ref "IC9") (pin "13") (pinfunction "2A2_13") (pintype "bidirectional"))
      (node (ref "IC9") (pin "15") (pinfunction "2A3_15") (pintype "bidirectional"))
      (node (ref "IC9") (pin "17") (pinfunction "2A4_17") (pintype "bidirectional"))
    )
    (net (code "116") (name "PWR_OE1") (class "Default")
      (node (ref "IC1") (pin "82") (pinfunction "P82_IOV1_82") (pintype "bidirectional"))
      (node (ref "IC9") (pin "1") (pinfunction "1NOE_1") (pintype "bidirectional"))
    )
    (net (code "117") (name "PWR_OE2") (class "Default")
      (node (ref "IC1") (pin "83") (pinfunction "P83_IO1_83") (pintype "bidirectional"))
      (node (ref "IC10") (pin "1") (pinfunction "1NOE_1") (pintype "bidirectional"))
    )
    (net (code "118") (name "PWR_OE3") (class "Default")
      (node (ref "IC1") (pin "84") (pinfunction "P84_IO1_84") (pintype "bidirectional"))
      (node (ref "IC9") (pin "19") (pinfunction "2NOE_19") (pintype "bidirectional"))
    )
    (net (code "119") (name "PWR_OE4") (class "Default")
      (node (ref "IC1") (pin "86") (pinfunction "P86_IOV1_86") (pintype "bidirectional"))
      (node (ref "IC10") (pin "19") (pinfunction "2NOE_19") (pintype "bidirectional"))
    )
    (net (code "120") (name "RELAY_ON") (class "Default")
      (node (ref "IC2") (pin "25") (pinfunction "PA25_25") (pintype "bidirectional"))
      (node (ref "R40") (pin "1") (pinfunction "1_1") (pintype "passive"))
    )
    (net (code "121") (name "SPCK") (class "Default")
      (node (ref "IC1") (pin "39") (pinfunction "P39_IGCK4_39") (pintype "bidirectional"))
      (node (ref "IC2") (pin "21") (pinfunction "PA14_21") (pintype "bidirectional"))
    )
    (net (code "122") (name "SSP_CLK") (class "Default")
      (node (ref "IC1") (pin "71") (pinfunction "P71_IO2_71") (pintype "bidirectional"))
      (node (ref "IC2") (pin "19") (pinfunction "PA16_19") (pintype "bidirectional"))
    )
    (net (code "123") (name "SSP_DIN") (class "Default")
      (node (ref "IC1") (pin "32") (pinfunction "P32_IO5_32") (pintype "bidirectional"))
      (node (ref "IC2") (pin "10") (pinfunction "PA18/AD1_10") (pintype "bidirectional"))
    )
    (net (code "124") (name "SSP_DOUT") (class "Default")
      (node (ref "IC1") (pin "34") (pinfunction "P34_IOV5_34") (pintype "bidirectional"))
      (node (ref "IC2") (pin "9") (pinfunction "PA17/AD0_9") (pintype "bidirectional"))
    )
    (net (code "125") (name "SSP_FRAME") (class "Default")
      (node (ref "IC1") (pin "31") (pinfunction "P31_IO5_31") (pintype "bidirectional"))
      (node (ref "IC2") (pin "20") (pinfunction "PA15_20") (pintype "bidirectional"))
    )
    (net (code "126") (name "USB_D+") (class "Default")
      (node (ref "D8") (pin "1") (pinfunction "K1_1") (pintype "bidirectional"))
      (node (ref "R5") (pin "1") (pinfunction "1_1") (pintype "passive"))
      (node (ref "SV1") (pin "3") (pinfunction "D+/3_3") (pintype "bidirectional"))
    )
    (net (code "127") (name "USB_D-") (class "Default")
      (node (ref "D8") (pin "2") (pinfunction "K2_2") (pintype "bidirectional"))
      (node (ref "R4") (pin "1") (pinfunction "1_1") (pintype "passive"))
      (node (ref "SV1") (pin "2") (pinfunction "D-/2_2") (pintype "bidirectional"))
    )
    (net (code "128") (name "USB_PU") (class "Default")
      (node (ref "IC2") (pin "23") (pinfunction "PA24_23") (pintype "bidirectional"))
      (node (ref "R6") (pin "2") (pinfunction "2_2") (pintype "passive"))
    )
    (net (code "129") (name "VDD") (class "Default")
      (node (ref "C21") (pin "1") (pinfunction "1_1") (pintype "passive"))
      (node (ref "C22") (pin "1") (pinfunction "1_1") (pintype "passive"))
      (node (ref "C23") (pin "1") (pinfunction "1_1") (pintype "passive"))
      (node (ref "C24") (pin "1") (pinfunction "1_1") (pintype "passive"))
      (node (ref "C37") (pin "+") (pinfunction "+_+") (pintype "passive"))
      (node (ref "C38") (pin "+") (pinfunction "+_+") (pintype "passive"))
      (node (ref "C44") (pin "1") (pinfunction "1_1") (pintype "passive"))
      (node (ref "C46") (pin "1") (pinfunction "1_1") (pintype "passive"))
      (node (ref "D7") (pin "3") (pinfunction "C_3") (pintype "passive"))
      (node (ref "IC10") (pin "20") (pinfunction "VDD_20") (pintype "bidirectional"))
      (node (ref "IC11") (pin "14") (pinfunction "VDD_14") (pintype "bidirectional"))
      (node (ref "IC12") (pin "4") (pinfunction "IN_4") (pintype "passive"))
      (node (ref "IC13") (pin "1") (pinfunction "VIN_1") (pintype "bidirectional"))
      (node (ref "IC14") (pin "8") (pinfunction "V+_8") (pintype "bidirectional"))
      (node (ref "IC5") (pin "8") (pinfunction "V+_8") (pintype "bidirectional"))
      (node (ref "IC6") (pin "4") (pinfunction "V+_4") (pintype "bidirectional"))
      (node (ref "IC8") (pin "11") (pinfunction "VDDD0_11") (pintype "bidirectional"))
      (node (ref "IC8") (pin "13") (pinfunction "VDDD1_13") (pintype "bidirectional"))
      (node (ref "IC8") (pin "14") (pinfunction "VDDA0_14") (pintype "bidirectional"))
      (node (ref "IC8") (pin "15") (pinfunction "VDDA1_15") (pintype "bidirectional"))
      (node (ref "IC8") (pin "18") (pinfunction "VDDA2_18") (pintype "bidirectional"))
      (node (ref "IC9") (pin "20") (pinfunction "VDD_20") (pintype "bidirectional"))
      (node (ref "Q2") (pin "6") (pinfunction "D_6") (pintype "passive"))
      (node (ref "R47") (pin "1") (pinfunction "1_1") (pintype "passive"))
      (node (ref "R52") (pin "2") (pinfunction "2_2") (pintype "passive"))
      (node (ref "R58") (pin "1") (pinfunction "1_1") (pintype "passive"))
      (node (ref "R9") (pin "2") (pinfunction "2_2") (pintype "passive"))
      (node (ref "RLY1") (pin "1") (pinfunction "P$1_1") (pintype "passive"))
    )
    (net (code "130") (name "VMID") (class "Default")
      (node (ref "C10") (pin "1") (pinfunction "1_1") (pintype "passive"))
      (node (ref "C45") (pin "1") (pinfunction "1_1") (pintype "passive"))
      (node (ref "IC6") (pin "1") (pinfunction "OUT_1") (pintype "output"))
      (node (ref "IC6") (pin "2") (pinfunction "-IN_2") (pintype "input"))
      (node (ref "R12") (pin "1") (pinfunction "1_1") (pintype "passive"))
      (node (ref "R13") (pin "1") (pinfunction "1_1") (pintype "passive"))
      (node (ref "R17") (pin "1") (pinfunction "1_1") (pintype "passive"))
      (node (ref "R19") (pin "1") (pinfunction "1_1") (pintype "passive"))
      (node (ref "R36") (pin "1") (pinfunction "1_1") (pintype "passive"))
      (node (ref "R38") (pin "1") (pinfunction "1_1") (pintype "passive"))
      (node (ref "R48") (pin "1") (pinfunction "1_1") (pintype "passive"))
      (node (ref "R49") (pin "1") (pinfunction "1_1") (pintype "passive"))
      (node (ref "R50") (pin "1") (pinfunction "1_1") (pintype "passive"))
      (node (ref "R51") (pin "1") (pinfunction "1_1") (pintype "passive"))
    )
    (net (code "131") (name "unconnected-(IC1-M0-Pad25)") (class "Default")
      (node (ref "IC1") (pin "25") (pinfunction "M0_25") (pintype "bidirectional"))
    )
    (net (code "132") (name "unconnected-(IC1-M1-Pad23)") (class "Default")
      (node (ref "IC1") (pin "23") (pinfunction "M1_23") (pintype "bidirectional"))
    )
    (net (code "133") (name "unconnected-(IC1-M2-Pad27)") (class "Default")
      (node (ref "IC1") (pin "27") (pinfunction "M2_27") (pintype "bidirectional"))
    )
    (net (code "134") (name "unconnected-(IC1-P3_IO7-Pad3)") (class "Default")
      (node (ref "IC1") (pin "3") (pinfunction "P3_IO7_3") (pintype "bidirectional"))
    )
    (net (code "135") (name "unconnected-(IC1-P4_IOV7-Pad4)") (class "Default")
      (node (ref "IC1") (pin "4") (pinfunction "P4_IOV7_4") (pintype "bidirectional"))
    )
    (net (code "136") (name "unconnected-(IC1-P5_IO7-Pad5)") (class "Default")
      (node (ref "IC1") (pin "5") (pinfunction "P5_IO7_5") (pintype "bidirectional"))
    )
    (net (code "137") (name "unconnected-(IC1-P6_IO7-Pad6)") (class "Default")
      (node (ref "IC1") (pin "6") (pinfunction "P6_IO7_6") (pintype "bidirectional"))
    )
    (net (code "138") (name "unconnected-(IC1-P7_IO7-Pad7)") (class "Default")
      (node (ref "IC1") (pin "7") (pinfunction "P7_IO7_7") (pintype "bidirectional"))
    )
    (net (code "139") (name "unconnected-(IC1-P8_IOV7-Pad8)") (class "Default")
      (node (ref "IC1") (pin "8") (pinfunction "P8_IOV7_8") (pintype "bidirectional"))
    )
    (net (code "140") (name "unconnected-(IC1-P9_IO7-Pad9)") (class "Default")
      (node (ref "IC1") (pin "9") (pinfunction "P9_IO7_9") (pintype "bidirectional"))
    )
    (net (code "141") (name "unconnected-(IC1-P10_IO7-Pad10)") (class "Default")
      (node (ref "IC1") (pin "10") (pinfunction "P10_IO7_10") (pintype "bidirectional"))
    )
    (net (code "142") (name "unconnected-(IC1-P13_IO6-Pad13)") (class "Default")
      (node (ref "IC1") (pin "13") (pinfunction "P13_IO6_13") (pintype "bidirectional"))
    )
    (net (code "143") (name "unconnected-(IC1-P15_IO6-Pad15)") (class "Default")
      (node (ref "IC1") (pin "15") (pinfunction "P15_IO6_15") (pintype "bidirectional"))
    )
    (net (code "144") (name "unconnected-(IC1-P16_IOV6-Pad16)") (class "Default")
      (node (ref "IC1") (pin "16") (pinfunction "P16_IOV6_16") (pintype "bidirectional"))
    )
    (net (code "145") (name "unconnected-(IC1-P17_IO6-Pad17)") (class "Default")
      (node (ref "IC1") (pin "17") (pinfunction "P17_IO6_17") (pintype "bidirectional"))
    )
    (net (code "146") (name "unconnected-(IC1-P18_IO6-Pad18)") (class "Default")
      (node (ref "IC1") (pin "18") (pinfunction "P18_IO6_18") (pintype "bidirectional"))
    )
    (net (code "147") (name "unconnected-(IC1-P19_IO6-Pad19)") (class "Default")
      (node (ref "IC1") (pin "19") (pinfunction "P19_IO6_19") (pintype "bidirectional"))
    )
    (net (code "148") (name "unconnected-(IC1-P20_IOV6-Pad20)") (class "Default")
      (node (ref "IC1") (pin "20") (pinfunction "P20_IOV6_20") (pintype "bidirectional"))
    )
    (net (code "149") (name "unconnected-(IC1-P21_IO6-Pad21)") (class "Default")
      (node (ref "IC1") (pin "21") (pinfunction "P21_IO6_21") (pintype "bidirectional"))
    )
    (net (code "150") (name "unconnected-(IC1-P30_IOV5-Pad30)") (class "Default")
      (node (ref "IC1") (pin "30") (pinfunction "P30_IOV5_30") (pintype "bidirectional"))
    )
    (net (code "151") (name "unconnected-(IC1-P41_IOV4-Pad41)") (class "Default")
      (node (ref "IC1") (pin "41") (pinfunction "P41_IOV4_41") (pintype "bidirectional"))
    )
    (net (code "152") (name "unconnected-(IC1-P45_IOV4-Pad45)") (class "Default")
      (node (ref "IC1") (pin "45") (pinfunction "P45_IOV4_45") (pintype "bidirectional"))
    )
    (net (code "153") (name "unconnected-(IC1-P59_IOV3-Pad59)") (class "Default")
      (node (ref "IC1") (pin "59") (pinfunction "P59_IOV3_59") (pintype "bidirectional"))
    )
    (net (code "154") (name "unconnected-(IC1-P65_IO2-Pad65)") (class "Default")
      (node (ref "IC1") (pin "65") (pinfunction "P65_IO2_65") (pintype "bidirectional"))
    )
    (net (code "155") (name "unconnected-(IC1-P66_IO2-Pad66)") (class "Default")
      (node (ref "IC1") (pin "66") (pinfunction "P66_IO2_66") (pintype "bidirectional"))
    )
    (net (code "156") (name "unconnected-(IC1-P67_IOV2-Pad67)") (class "Default")
      (node (ref "IC1") (pin "67") (pinfunction "P67_IOV2_67") (pintype "bidirectional"))
    )
    (net (code "157") (name "unconnected-(IC1-P68_IO2-Pad68)") (class "Default")
      (node (ref "IC1") (pin "68") (pinfunction "P68_IO2_68") (pintype "bidirectional"))
    )
    (net (code "158") (name "unconnected-(IC1-P69_IO2-Pad69)") (class "Default")
      (node (ref "IC1") (pin "69") (pinfunction "P69_IO2_69") (pintype "bidirectional"))
    )
    (net (code "159") (name "unconnected-(IC1-P70_IO2-Pad70)") (class "Default")
      (node (ref "IC1") (pin "70") (pinfunction "P70_IO2_70") (pintype "bidirectional"))
    )
    (net (code "160") (name "unconnected-(IC1-P72_IOV2-Pad72)") (class "Default")
      (node (ref "IC1") (pin "72") (pinfunction "P72_IOV2_72") (pintype "bidirectional"))
    )
    (net (code "161") (name "unconnected-(IC1-P95_IO0-Pad95)") (class "Default")
      (node (ref "IC1") (pin "95") (pinfunction "P95_IO0_95") (pintype "bidirectional"))
    )
    (net (code "162") (name "unconnected-(IC1-P96_IO0-Pad96)") (class "Default")
      (node (ref "IC1") (pin "96") (pinfunction "P96_IO0_96") (pintype "bidirectional"))
    )
    (net (code "163") (name "unconnected-(IC1-P97_IOV0-Pad97)") (class "Default")
      (node (ref "IC1") (pin "97") (pinfunction "P97_IOV0_97") (pintype "bidirectional"))
    )
    (net (code "164") (name "unconnected-(IC1-P98_IO0-Pad98)") (class "Default")
      (node (ref "IC1") (pin "98") (pinfunction "P98_IO0_98") (pintype "bidirectional"))
    )
    (net (code "165") (name "unconnected-(IC2-AD6-Pad5)") (class "Default")
      (node (ref "IC2") (pin "5") (pinfunction "AD6_5") (pintype "bidirectional"))
    )
    (net (code "166") (name "unconnected-(IC2-AD7-Pad6)") (class "Default")
      (node (ref "IC2") (pin "6") (pinfunction "AD7_6") (pintype "bidirectional"))
    )
    (net (code "167") (name "unconnected-(IC2-ERASE-Pad55)") (class "Default")
      (node (ref "IC2") (pin "55") (pinfunction "ERASE_55") (pintype "bidirectional"))
    )
    (net (code "168") (name "unconnected-(IC2-JTAGSEL-Pad50)") (class "Default")
      (node (ref "IC2") (pin "50") (pinfunction "JTAGSEL_50") (pintype "bidirectional"))
    )
    (net (code "169") (name "unconnected-(IC2-PA1-Pad47)") (class "Default")
      (node (ref "IC2") (pin "47") (pinfunction "PA1_47") (pintype "bidirectional"))
    )
    (net (code "170") (name "unconnected-(IC2-PA5-Pad35)") (class "Default")
      (node (ref "IC2") (pin "35") (pinfunction "PA5_35") (pintype "bidirectional"))
    )
    (net (code "171") (name "unconnected-(IC2-PA7-Pad32)") (class "Default")
      (node (ref "IC2") (pin "32") (pinfunction "PA7_32") (pintype "bidirectional"))
    )
    (net (code "172") (name "unconnected-(IC2-PA10-Pad29)") (class "Default")
      (node (ref "IC2") (pin "29") (pinfunction "PA10_29") (pintype "bidirectional"))
    )
    (net (code "173") (name "unconnected-(IC2-TST-Pad40)") (class "Default")
      (node (ref "IC2") (pin "40") (pinfunction "TST_40") (pintype "bidirectional"))
    )
    (net (code "174") (name "unconnected-(IC3-NR-Pad4)") (class "Default")
      (node (ref "IC3") (pin "4") (pinfunction "NR_4") (pintype "bidirectional"))
    )
    (net (code "175") (name "unconnected-(IC6D-OUT-Pad14)") (class "Default")
      (node (ref "IC6") (pin "14") (pinfunction "OUT_14") (pintype "output"))
    )
    (net (code "176") (name "unconnected-(IC8-REFBS-Pad22)") (class "Default")
      (node (ref "IC8") (pin "22") (pinfunction "REFBS_22") (pintype "bidirectional"))
    )
    (net (code "177") (name "unconnected-(IC8-REFTS-Pad16)") (class "Default")
      (node (ref "IC8") (pin "16") (pinfunction "REFTS_16") (pintype "bidirectional"))
    )
    (net (code "178") (name "unconnected-(IC12-BYP-Pad1)") (class "Default")
      (node (ref "IC12") (pin "1") (pinfunction "BYP_1") (pintype "passive"))
    )
    (net (code "179") (name "unconnected-(IC12-{slash}ERROR-Pad7)") (class "Default")
      (node (ref "IC12") (pin "7") (pinfunction "/ERROR_7") (pintype "passive"))
    )
    (net (code "180") (name "unconnected-(IC13-NR-Pad4)") (class "Default")
      (node (ref "IC13") (pin "4") (pinfunction "NR_4") (pintype "bidirectional"))
    )
    (net (code "181") (name "unconnected-(SV1-ID{slash}4-Pad4)") (class "Default")
      (node (ref "SV1") (pin "4") (pinfunction "ID/4_4") (pintype "bidirectional"))
    )
    (net (code "182") (name "unconnected-(SV3-Pad2)") (class "Default")
      (node (ref "SV3") (pin "2") (pinfunction "2_2") (pintype "passive"))
    )
    (net (code "183") (name "unconnected-(SV3-Pad3)") (class "Default")
      (node (ref "SV3") (pin "3") (pinfunction "3_3") (pintype "passive"))
    )
    (net (code "184") (name "unconnected-(SV3-Pad11)") (class "Default")
      (node (ref "SV3") (pin "11") (pinfunction "11_11") (pintype "passive"))
    )
    (net (code "185") (name "unconnected-(SV3-Pad15)") (class "Default")
      (node (ref "SV3") (pin "15") (pinfunction "15_15") (pintype "passive"))
    )
    (net (code "186") (name "unconnected-(SV3-Pad17)") (class "Default")
      (node (ref "SV3") (pin "17") (pinfunction "17_17") (pintype "passive"))
    )
    (net (code "187") (name "unconnected-(SV3-Pad19)") (class "Default")
      (node (ref "SV3") (pin "19") (pinfunction "19_19") (pintype "passive"))
    )
  )
)
